# nanobone.net
KiCad netlist of a schematic drawn in EAGLE
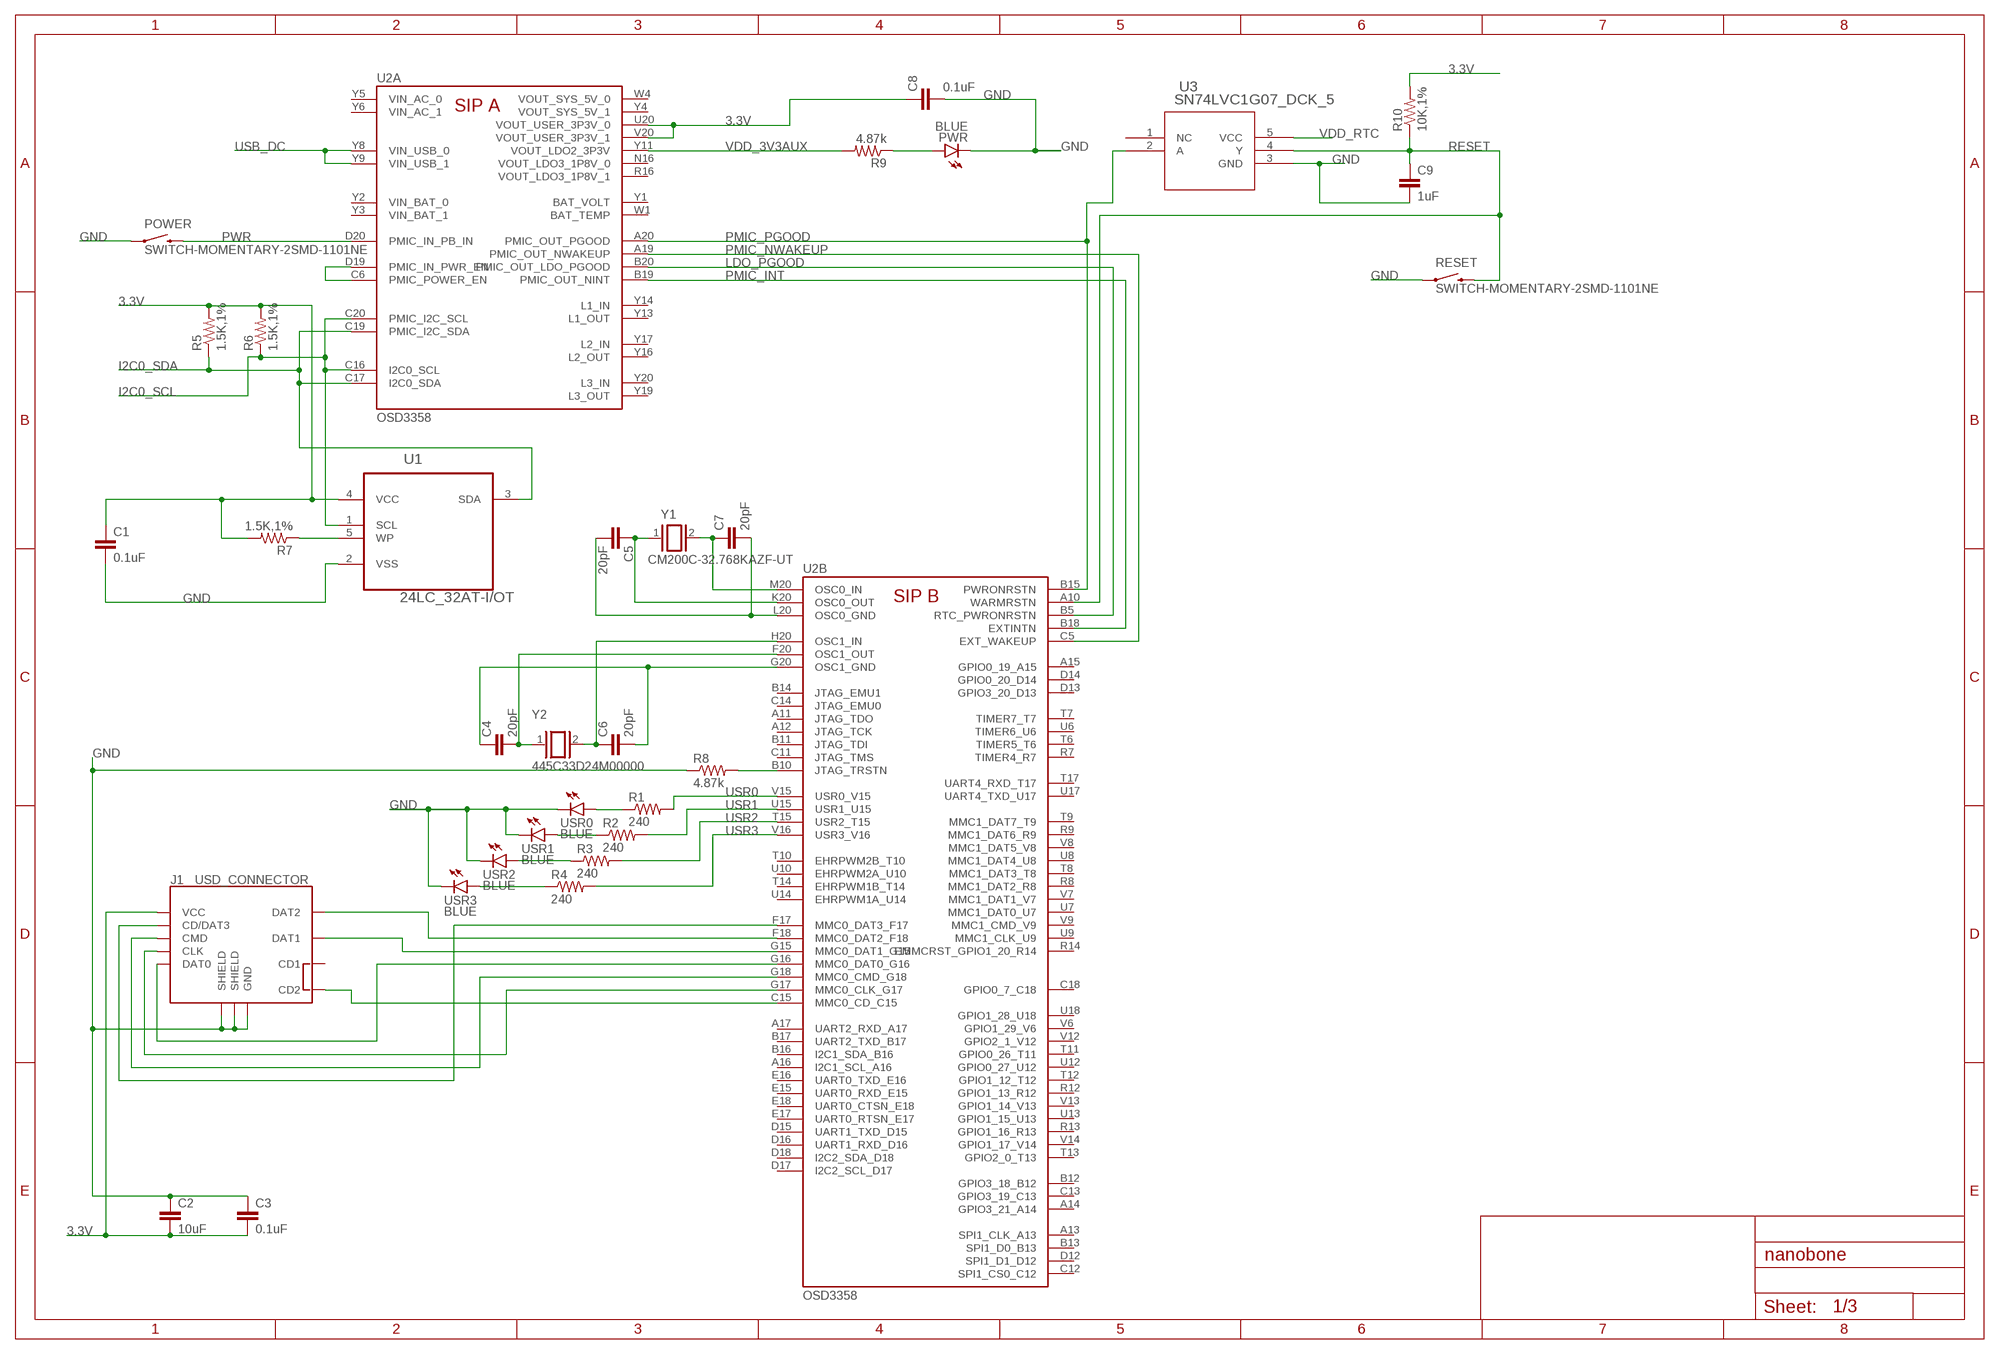
[diagram p0: schematic, sheet 1]
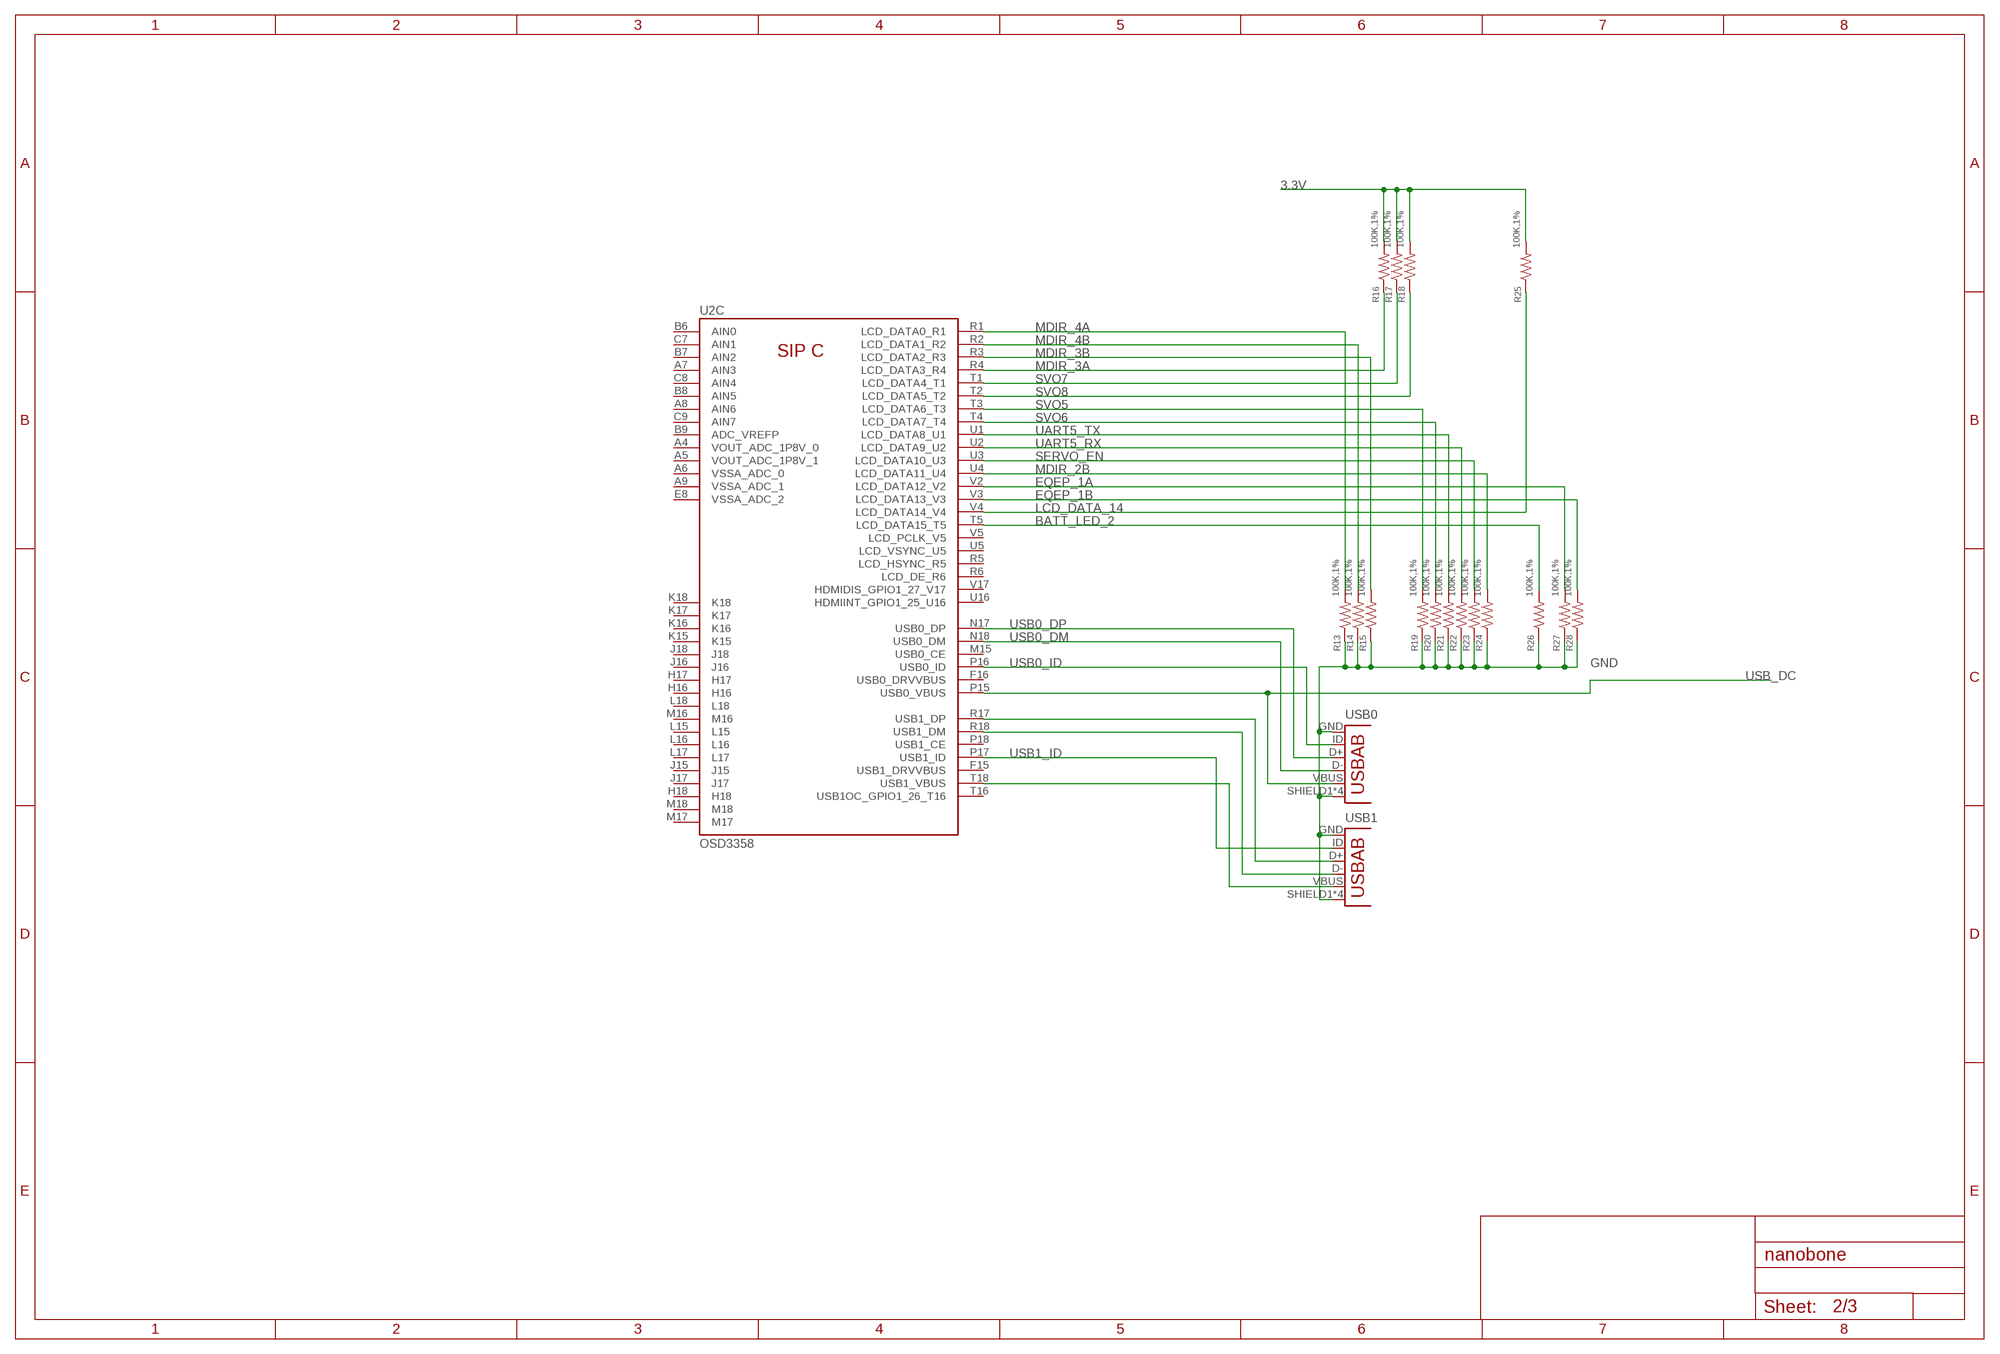
[diagram p1: schematic, sheet 2]
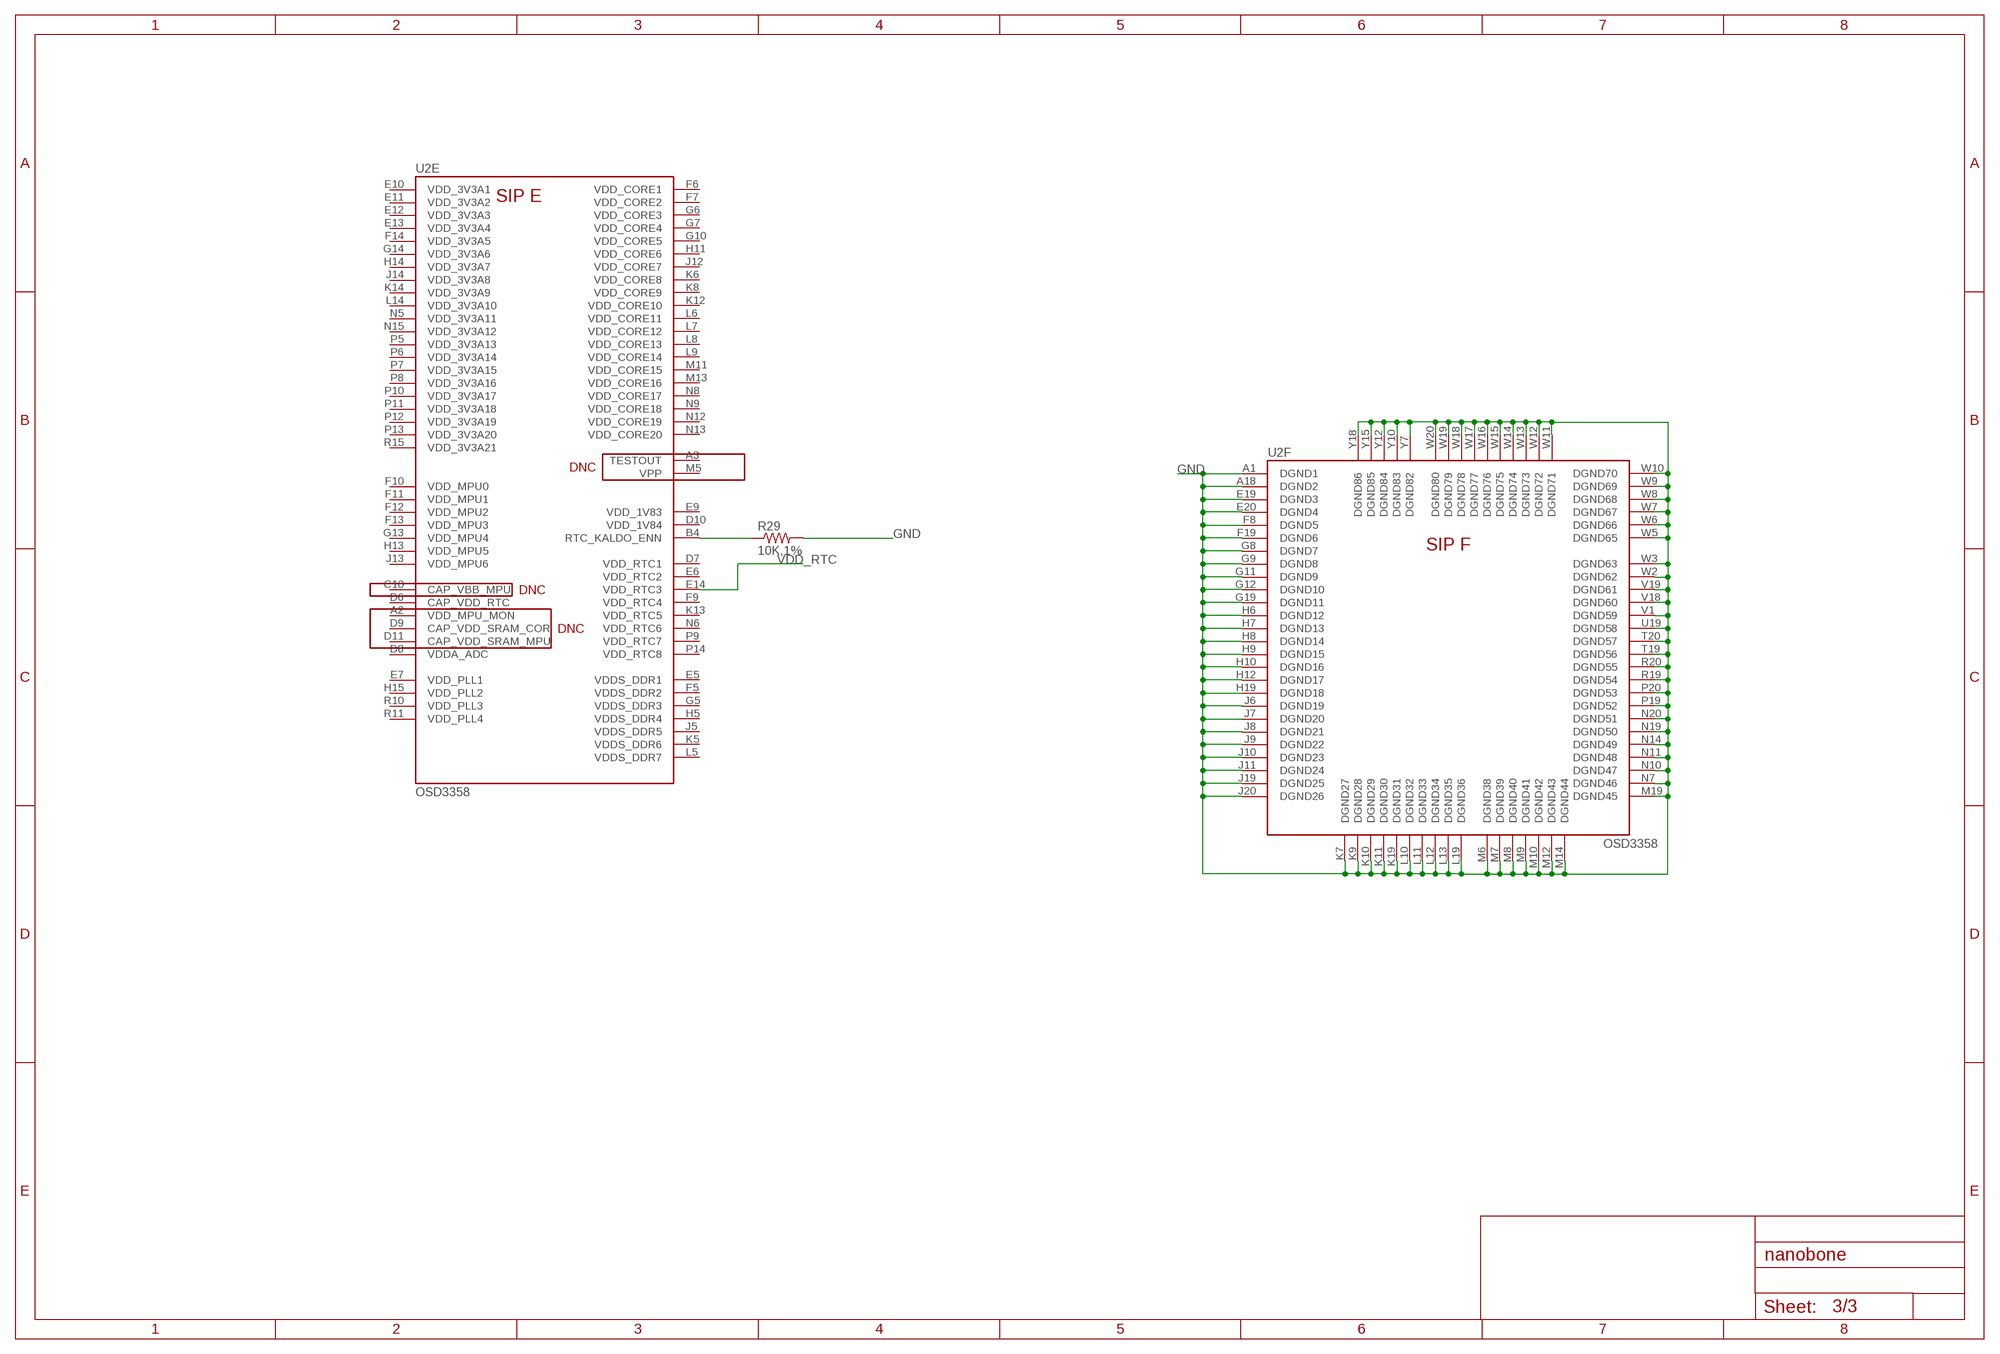
[diagram p2: schematic, sheet 3]

(export (version "E")
  (design (tool "Eeschema 10.0.6"))
  (components
    (comp (ref "R13")
      (value "100K,1%")
      (footprint "eagle-import:0402-RES")
      (libsource (lib "eagle-import") (part "RESISTOR0402-RES"))
    )
    (comp (ref "R14")
      (value "100K,1%")
      (footprint "eagle-import:0402-RES")
      (libsource (lib "eagle-import") (part "RESISTOR0402-RES"))
    )
    (comp (ref "R15")
      (value "100K,1%")
      (footprint "eagle-import:0402-RES")
      (libsource (lib "eagle-import") (part "RESISTOR0402-RES"))
    )
    (comp (ref "R16")
      (value "100K,1%")
      (footprint "eagle-import:0402-RES")
      (libsource (lib "eagle-import") (part "RESISTOR0402-RES"))
    )
    (comp (ref "R17")
      (value "100K,1%")
      (footprint "eagle-import:0402-RES")
      (libsource (lib "eagle-import") (part "RESISTOR0402-RES"))
    )
    (comp (ref "R18")
      (value "100K,1%")
      (footprint "eagle-import:0402-RES")
      (libsource (lib "eagle-import") (part "RESISTOR0402-RES"))
    )
    (comp (ref "R19")
      (value "100K,1%")
      (footprint "eagle-import:0402-RES")
      (libsource (lib "eagle-import") (part "RESISTOR0402-RES"))
    )
    (comp (ref "R20")
      (value "100K,1%")
      (footprint "eagle-import:0402-RES")
      (libsource (lib "eagle-import") (part "RESISTOR0402-RES"))
    )
    (comp (ref "R21")
      (value "100K,1%")
      (footprint "eagle-import:0402-RES")
      (libsource (lib "eagle-import") (part "RESISTOR0402-RES"))
    )
    (comp (ref "R22")
      (value "100K,1%")
      (footprint "eagle-import:0402-RES")
      (libsource (lib "eagle-import") (part "RESISTOR0402-RES"))
    )
    (comp (ref "R23")
      (value "100K,1%")
      (footprint "eagle-import:0402-RES")
      (libsource (lib "eagle-import") (part "RESISTOR0402-RES"))
    )
    (comp (ref "R24")
      (value "100K,1%")
      (footprint "eagle-import:0402-RES")
      (libsource (lib "eagle-import") (part "RESISTOR0402-RES"))
    )
    (comp (ref "R25")
      (value "100K,1%")
      (footprint "eagle-import:0402-RES")
      (libsource (lib "eagle-import") (part "RESISTOR0402-RES"))
    )
    (comp (ref "R26")
      (value "100K,1%")
      (footprint "eagle-import:0402-RES")
      (libsource (lib "eagle-import") (part "RESISTOR0402-RES"))
    )
    (comp (ref "R27")
      (value "100K,1%")
      (footprint "eagle-import:0402-RES")
      (libsource (lib "eagle-import") (part "RESISTOR0402-RES"))
    )
    (comp (ref "R28")
      (value "100K,1%")
      (footprint "eagle-import:0402-RES")
      (libsource (lib "eagle-import") (part "RESISTOR0402-RES"))
    )
    (comp (ref "U2")
      (value "OSD3358")
      (footprint "eagle-import:OSD3358")
      (libsource (lib "eagle-import") (part "OSD3358"))
    )
    (comp (ref "USB0")
      (value "USB-AB")
      (footprint "eagle-import:USB-AB-MICRO-SMD")
      (libsource (lib "eagle-import") (part "USB-AB"))
    )
    (comp (ref "USB1")
      (value "USB-AB")
      (footprint "eagle-import:USB-AB-MICRO-SMD")
      (libsource (lib "eagle-import") (part "USB-AB"))
    )
    (comp (ref "C1")
      (value "0.1uF")
      (footprint "eagle-import:0402-CAP")
      (libsource (lib "eagle-import") (part "CAP0402-CAP"))
    )
    (comp (ref "C2")
      (value "10uF")
      (footprint "eagle-import:0805")
      (libsource (lib "eagle-import") (part "CAP0805"))
    )
    (comp (ref "C3")
      (value "0.1uF")
      (footprint "eagle-import:0402-CAP")
      (libsource (lib "eagle-import") (part "CAP0402-CAP"))
    )
    (comp (ref "C4")
      (value "20pF")
      (footprint "eagle-import:0402-CAP")
      (libsource (lib "eagle-import") (part "CAP0402-CAP"))
    )
    (comp (ref "C5")
      (value "20pF")
      (footprint "eagle-import:0402-CAP")
      (libsource (lib "eagle-import") (part "CAP0402-CAP"))
    )
    (comp (ref "C6")
      (value "20pF")
      (footprint "eagle-import:0402-CAP")
      (libsource (lib "eagle-import") (part "CAP0402-CAP"))
    )
    (comp (ref "C7")
      (value "20pF")
      (footprint "eagle-import:0402-CAP")
      (libsource (lib "eagle-import") (part "CAP0402-CAP"))
    )
    (comp (ref "C8")
      (value "0.1uF")
      (footprint "eagle-import:0402-CAP")
      (libsource (lib "eagle-import") (part "CAP0402-CAP"))
    )
    (comp (ref "C9")
      (value "1uF")
      (footprint "eagle-import:0402-CAP")
      (libsource (lib "eagle-import") (part "CAP0402-CAP"))
    )
    (comp (ref "J1")
      (value "USD_CONNECTOR")
      (footprint "eagle-import:MICRO-SD-SOCKET-PP")
      (libsource (lib "eagle-import") (part "USD_CONNECTOR"))
    )
    (comp (ref "POWER")
      (value "SWITCH-MOMENTARY-2SMD-1101NE")
      (footprint "eagle-import:TACTILE-SWITCH-1101NE")
      (libsource (lib "eagle-import") (part "SWITCH-MOMENTARY-2SMD-1101NE"))
    )
    (comp (ref "PWR")
      (value "BLUE")
      (footprint "eagle-import:0402-LED")
      (libsource (lib "eagle-import") (part "LED0402"))
    )
    (comp (ref "R1")
      (value "240")
      (footprint "eagle-import:0402-RES")
      (libsource (lib "eagle-import") (part "RESISTOR0402-RES"))
    )
    (comp (ref "R2")
      (value "240")
      (footprint "eagle-import:0402-RES")
      (libsource (lib "eagle-import") (part "RESISTOR0402-RES"))
    )
    (comp (ref "R3")
      (value "240")
      (footprint "eagle-import:0402-RES")
      (libsource (lib "eagle-import") (part "RESISTOR0402-RES"))
    )
    (comp (ref "R4")
      (value "240")
      (footprint "eagle-import:0402-RES")
      (libsource (lib "eagle-import") (part "RESISTOR0402-RES"))
    )
    (comp (ref "R5")
      (value "1.5K,1%")
      (footprint "eagle-import:0402-RES")
      (libsource (lib "eagle-import") (part "RESISTOR0402-RES"))
    )
    (comp (ref "R6")
      (value "1.5K,1%")
      (footprint "eagle-import:0402-RES")
      (libsource (lib "eagle-import") (part "RESISTOR0402-RES"))
    )
    (comp (ref "R7")
      (value "1.5K,1%")
      (footprint "eagle-import:0402-RES")
      (libsource (lib "eagle-import") (part "RESISTOR0402-RES"))
    )
    (comp (ref "R8")
      (value "4.87k")
      (footprint "eagle-import:0402-RES")
      (libsource (lib "eagle-import") (part "RESISTOR0402-RES"))
    )
    (comp (ref "R9")
      (value "4.87k")
      (footprint "eagle-import:0402-RES")
      (libsource (lib "eagle-import") (part "RESISTOR0402-RES"))
    )
    (comp (ref "R10")
      (value "10K,1%")
      (footprint "eagle-import:0402-RES")
      (libsource (lib "eagle-import") (part "RESISTOR0402-RES"))
    )
    (comp (ref "RESET")
      (value "SWITCH-MOMENTARY-2SMD-1101NE")
      (footprint "eagle-import:TACTILE-SWITCH-1101NE")
      (libsource (lib "eagle-import") (part "SWITCH-MOMENTARY-2SMD-1101NE"))
    )
    (comp (ref "U1")
      (value "24LC_32AT-I/OT")
      (footprint "eagle-import:SOT95P290X145-5N")
      (fields (field (name "MPN") "24LC32AT-I/OT"))
      (libsource (lib "eagle-import") (part "24LC_32AT-I/OT"))
    )
    (comp (ref "U3")
      (value "SN74LVC1G07_DCK_5")
      (footprint "eagle-import:DCK5")
      (fields
        (field (name "GENERIC_PART_NUMBER") "SN74LVC1G07")
        (field (name "MANUFACTURER") "Texas Instruments")
        (field (name "MANUFACTURER_PART_NUMBER") "sn74lvc1g07_dck_5")
      )
      (libsource (lib "eagle-import") (part "SN74LVC1G07_DCK_5"))
    )
    (comp (ref "USR0")
      (value "BLUE")
      (footprint "eagle-import:0402-LED")
      (libsource (lib "eagle-import") (part "LED0402"))
    )
    (comp (ref "USR1")
      (value "BLUE")
      (footprint "eagle-import:0402-LED")
      (libsource (lib "eagle-import") (part "LED0402"))
    )
    (comp (ref "USR2")
      (value "BLUE")
      (footprint "eagle-import:0402-LED")
      (libsource (lib "eagle-import") (part "LED0402"))
    )
    (comp (ref "USR3")
      (value "BLUE")
      (footprint "eagle-import:0402-LED")
      (libsource (lib "eagle-import") (part "LED0402"))
    )
    (comp (ref "Y1")
      (value "CM200C-32.768KAZF-UT")
      (footprint "eagle-import:CM200C-32.768KAZF-UT")
      (libsource (lib "eagle-import") (part "CM200C-32.768KAZF-UT"))
    )
    (comp (ref "Y2")
      (value "445C33D24M00000")
      (footprint "eagle-import:445C33D24M00000")
      (libsource (lib "eagle-import") (part "445C33D24M00000"))
    )
    (comp (ref "R29")
      (value "10K,1%")
      (footprint "eagle-import:0402-RES")
      (libsource (lib "eagle-import") (part "RESISTOR0402-RES"))
    )
  )
  (nets
    (net (code "1") (name "3.3V") (class "Default")
      (node (ref "C1") (pin "1") (pinfunction "1_1") (pintype "passive"))
      (node (ref "C2") (pin "2") (pinfunction "2_2") (pintype "passive"))
      (node (ref "C3") (pin "2") (pinfunction "2_2") (pintype "passive"))
      (node (ref "C8") (pin "1") (pinfunction "1_1") (pintype "passive"))
      (node (ref "J1") (pin "VCC") (pinfunction "VCC_VCC") (pintype "bidirectional"))
      (node (ref "R10") (pin "2") (pinfunction "2_2") (pintype "passive"))
      (node (ref "R16") (pin "2") (pinfunction "2_2") (pintype "passive"))
      (node (ref "R17") (pin "2") (pinfunction "2_2") (pintype "passive"))
      (node (ref "R18") (pin "2") (pinfunction "2_2") (pintype "passive"))
      (node (ref "R25") (pin "2") (pinfunction "2_2") (pintype "passive"))
      (node (ref "R5") (pin "2") (pinfunction "2_2") (pintype "passive"))
      (node (ref "R6") (pin "2") (pinfunction "2_2") (pintype "passive"))
      (node (ref "R7") (pin "2") (pinfunction "2_2") (pintype "passive"))
      (node (ref "U1") (pin "4") (pinfunction "VCC_4") (pintype "power_in"))
      (node (ref "U2") (pin "U20") (pinfunction "VOUT_USER_3P3V_0_U20") (pintype "power_in"))
      (node (ref "U2") (pin "V20") (pinfunction "VOUT_USER_3P3V_1_V20") (pintype "power_in"))
    )
    (net (code "2") (name "BATT_LED_2") (class "Default")
      (node (ref "R26") (pin "2") (pinfunction "2_2") (pintype "passive"))
      (node (ref "U2") (pin "T5") (pinfunction "LCD_DATA15_T5_T5") (pintype "bidirectional"))
    )
    (net (code "3") (name "EQEP_1A") (class "Default")
      (node (ref "R27") (pin "2") (pinfunction "2_2") (pintype "passive"))
      (node (ref "U2") (pin "V2") (pinfunction "LCD_DATA12_V2_V2") (pintype "bidirectional"))
    )
    (net (code "4") (name "EQEP_1B") (class "Default")
      (node (ref "R28") (pin "2") (pinfunction "2_2") (pintype "passive"))
      (node (ref "U2") (pin "V3") (pinfunction "LCD_DATA13_V3_V3") (pintype "bidirectional"))
    )
    (net (code "5") (name "GND") (class "Default")
      (node (ref "C1") (pin "2") (pinfunction "2_2") (pintype "passive"))
      (node (ref "C2") (pin "1") (pinfunction "1_1") (pintype "passive"))
      (node (ref "C3") (pin "1") (pinfunction "1_1") (pintype "passive"))
      (node (ref "C8") (pin "2") (pinfunction "2_2") (pintype "passive"))
      (node (ref "C9") (pin "2") (pinfunction "2_2") (pintype "passive"))
      (node (ref "J1") (pin "GND") (pinfunction "GND_GND") (pintype "bidirectional"))
      (node (ref "J1") (pin "GND1") (pinfunction "SHIELD_GND1") (pintype "bidirectional"))
      (node (ref "J1") (pin "GND3") (pinfunction "SHIELD_GND3") (pintype "bidirectional"))
      (node (ref "POWER") (pin "1") (pinfunction "1_1") (pintype "passive"))
      (node (ref "PWR") (pin "C") (pinfunction "C_C") (pintype "passive"))
      (node (ref "R13") (pin "1") (pinfunction "1_1") (pintype "passive"))
      (node (ref "R14") (pin "1") (pinfunction "1_1") (pintype "passive"))
      (node (ref "R15") (pin "1") (pinfunction "1_1") (pintype "passive"))
      (node (ref "R19") (pin "1") (pinfunction "1_1") (pintype "passive"))
      (node (ref "R20") (pin "1") (pinfunction "1_1") (pintype "passive"))
      (node (ref "R21") (pin "1") (pinfunction "1_1") (pintype "passive"))
      (node (ref "R22") (pin "1") (pinfunction "1_1") (pintype "passive"))
      (node (ref "R23") (pin "1") (pinfunction "1_1") (pintype "passive"))
      (node (ref "R24") (pin "1") (pinfunction "1_1") (pintype "passive"))
      (node (ref "R26") (pin "1") (pinfunction "1_1") (pintype "passive"))
      (node (ref "R27") (pin "1") (pinfunction "1_1") (pintype "passive"))
      (node (ref "R28") (pin "1") (pinfunction "1_1") (pintype "passive"))
      (node (ref "R29") (pin "2") (pinfunction "2_2") (pintype "passive"))
      (node (ref "R8") (pin "1") (pinfunction "1_1") (pintype "passive"))
      (node (ref "RESET") (pin "1") (pinfunction "1_1") (pintype "passive"))
      (node (ref "U1") (pin "2") (pinfunction "VSS_2") (pintype "passive"))
      (node (ref "U2") (pin "A1") (pinfunction "DGND1_A1") (pintype "bidirectional"))
      (node (ref "U2") (pin "A18") (pinfunction "DGND2_A18") (pintype "bidirectional"))
      (node (ref "U2") (pin "E19") (pinfunction "DGND3_E19") (pintype "bidirectional"))
      (node (ref "U2") (pin "E20") (pinfunction "DGND4_E20") (pintype "bidirectional"))
      (node (ref "U2") (pin "F19") (pinfunction "DGND6_F19") (pintype "bidirectional"))
      (node (ref "U2") (pin "F8") (pinfunction "DGND5_F8") (pintype "bidirectional"))
      (node (ref "U2") (pin "G11") (pinfunction "DGND9_G11") (pintype "bidirectional"))
      (node (ref "U2") (pin "G12") (pinfunction "DGND10_G12") (pintype "bidirectional"))
      (node (ref "U2") (pin "G19") (pinfunction "DGND11_G19") (pintype "bidirectional"))
      (node (ref "U2") (pin "G8") (pinfunction "DGND7_G8") (pintype "bidirectional"))
      (node (ref "U2") (pin "G9") (pinfunction "DGND8_G9") (pintype "bidirectional"))
      (node (ref "U2") (pin "H10") (pinfunction "DGND16_H10") (pintype "bidirectional"))
      (node (ref "U2") (pin "H12") (pinfunction "DGND17_H12") (pintype "bidirectional"))
      (node (ref "U2") (pin "H19") (pinfunction "DGND18_H19") (pintype "bidirectional"))
      (node (ref "U2") (pin "H6") (pinfunction "DGND12_H6") (pintype "bidirectional"))
      (node (ref "U2") (pin "H7") (pinfunction "DGND13_H7") (pintype "bidirectional"))
      (node (ref "U2") (pin "H8") (pinfunction "DGND14_H8") (pintype "bidirectional"))
      (node (ref "U2") (pin "H9") (pinfunction "DGND15_H9") (pintype "bidirectional"))
      (node (ref "U2") (pin "J10") (pinfunction "DGND23_J10") (pintype "bidirectional"))
      (node (ref "U2") (pin "J11") (pinfunction "DGND24_J11") (pintype "bidirectional"))
      (node (ref "U2") (pin "J19") (pinfunction "DGND25_J19") (pintype "bidirectional"))
      (node (ref "U2") (pin "J20") (pinfunction "DGND26_J20") (pintype "bidirectional"))
      (node (ref "U2") (pin "J6") (pinfunction "DGND19_J6") (pintype "bidirectional"))
      (node (ref "U2") (pin "J7") (pinfunction "DGND20_J7") (pintype "bidirectional"))
      (node (ref "U2") (pin "J8") (pinfunction "DGND21_J8") (pintype "bidirectional"))
      (node (ref "U2") (pin "J9") (pinfunction "DGND22_J9") (pintype "bidirectional"))
      (node (ref "U2") (pin "K10") (pinfunction "DGND29_K10") (pintype "bidirectional"))
      (node (ref "U2") (pin "K11") (pinfunction "DGND30_K11") (pintype "bidirectional"))
      (node (ref "U2") (pin "K19") (pinfunction "DGND31_K19") (pintype "bidirectional"))
      (node (ref "U2") (pin "K7") (pinfunction "DGND27_K7") (pintype "bidirectional"))
      (node (ref "U2") (pin "K9") (pinfunction "DGND28_K9") (pintype "bidirectional"))
      (node (ref "U2") (pin "L10") (pinfunction "DGND32_L10") (pintype "bidirectional"))
      (node (ref "U2") (pin "L11") (pinfunction "DGND33_L11") (pintype "bidirectional"))
      (node (ref "U2") (pin "L12") (pinfunction "DGND34_L12") (pintype "bidirectional"))
      (node (ref "U2") (pin "L13") (pinfunction "DGND35_L13") (pintype "bidirectional"))
      (node (ref "U2") (pin "L19") (pinfunction "DGND36_L19") (pintype "bidirectional"))
      (node (ref "U2") (pin "M10") (pinfunction "DGND42_M10") (pintype "bidirectional"))
      (node (ref "U2") (pin "M12") (pinfunction "DGND43_M12") (pintype "bidirectional"))
      (node (ref "U2") (pin "M14") (pinfunction "DGND44_M14") (pintype "bidirectional"))
      (node (ref "U2") (pin "M19") (pinfunction "DGND45_M19") (pintype "bidirectional"))
      (node (ref "U2") (pin "M6") (pinfunction "DGND38_M6") (pintype "bidirectional"))
      (node (ref "U2") (pin "M7") (pinfunction "DGND39_M7") (pintype "bidirectional"))
      (node (ref "U2") (pin "M8") (pinfunction "DGND40_M8") (pintype "bidirectional"))
      (node (ref "U2") (pin "M9") (pinfunction "DGND41_M9") (pintype "bidirectional"))
      (node (ref "U2") (pin "N10") (pinfunction "DGND47_N10") (pintype "bidirectional"))
      (node (ref "U2") (pin "N11") (pinfunction "DGND48_N11") (pintype "bidirectional"))
      (node (ref "U2") (pin "N14") (pinfunction "DGND49_N14") (pintype "bidirectional"))
      (node (ref "U2") (pin "N19") (pinfunction "DGND50_N19") (pintype "bidirectional"))
      (node (ref "U2") (pin "N20") (pinfunction "DGND51_N20") (pintype "bidirectional"))
      (node (ref "U2") (pin "N7") (pinfunction "DGND46_N7") (pintype "bidirectional"))
      (node (ref "U2") (pin "P19") (pinfunction "DGND52_P19") (pintype "bidirectional"))
      (node (ref "U2") (pin "P20") (pinfunction "DGND53_P20") (pintype "bidirectional"))
      (node (ref "U2") (pin "R19") (pinfunction "DGND54_R19") (pintype "bidirectional"))
      (node (ref "U2") (pin "R20") (pinfunction "DGND55_R20") (pintype "bidirectional"))
      (node (ref "U2") (pin "T19") (pinfunction "DGND56_T19") (pintype "bidirectional"))
      (node (ref "U2") (pin "T20") (pinfunction "DGND57_T20") (pintype "bidirectional"))
      (node (ref "U2") (pin "U19") (pinfunction "DGND58_U19") (pintype "bidirectional"))
      (node (ref "U2") (pin "V1") (pinfunction "DGND59_V1") (pintype "bidirectional"))
      (node (ref "U2") (pin "V18") (pinfunction "DGND60_V18") (pintype "bidirectional"))
      (node (ref "U2") (pin "V19") (pinfunction "DGND61_V19") (pintype "bidirectional"))
      (node (ref "U2") (pin "W10") (pinfunction "DGND70_W10") (pintype "bidirectional"))
      (node (ref "U2") (pin "W11") (pinfunction "DGND71_W11") (pintype "bidirectional"))
      (node (ref "U2") (pin "W12") (pinfunction "DGND72_W12") (pintype "bidirectional"))
      (node (ref "U2") (pin "W13") (pinfunction "DGND73_W13") (pintype "bidirectional"))
      (node (ref "U2") (pin "W14") (pinfunction "DGND74_W14") (pintype "bidirectional"))
      (node (ref "U2") (pin "W15") (pinfunction "DGND75_W15") (pintype "bidirectional"))
      (node (ref "U2") (pin "W16") (pinfunction "DGND76_W16") (pintype "bidirectional"))
      (node (ref "U2") (pin "W17") (pinfunction "DGND77_W17") (pintype "bidirectional"))
      (node (ref "U2") (pin "W18") (pinfunction "DGND78_W18") (pintype "bidirectional"))
      (node (ref "U2") (pin "W19") (pinfunction "DGND79_W19") (pintype "bidirectional"))
      (node (ref "U2") (pin "W2") (pinfunction "DGND62_W2") (pintype "bidirectional"))
      (node (ref "U2") (pin "W20") (pinfunction "DGND80_W20") (pintype "bidirectional"))
      (node (ref "U2") (pin "W3") (pinfunction "DGND63_W3") (pintype "bidirectional"))
      (node (ref "U2") (pin "W5") (pinfunction "DGND65_W5") (pintype "bidirectional"))
      (node (ref "U2") (pin "W6") (pinfunction "DGND66_W6") (pintype "bidirectional"))
      (node (ref "U2") (pin "W7") (pinfunction "DGND67_W7") (pintype "bidirectional"))
      (node (ref "U2") (pin "W8") (pinfunction "DGND68_W8") (pintype "bidirectional"))
      (node (ref "U2") (pin "W9") (pinfunction "DGND69_W9") (pintype "bidirectional"))
      (node (ref "U2") (pin "Y10") (pinfunction "DGND83_Y10") (pintype "bidirectional"))
      (node (ref "U2") (pin "Y12") (pinfunction "DGND84_Y12") (pintype "bidirectional"))
      (node (ref "U2") (pin "Y15") (pinfunction "DGND85_Y15") (pintype "bidirectional"))
      (node (ref "U2") (pin "Y18") (pinfunction "DGND86_Y18") (pintype "bidirectional"))
      (node (ref "U2") (pin "Y7") (pinfunction "DGND82_Y7") (pintype "bidirectional"))
      (node (ref "U3") (pin "3") (pinfunction "GND_3") (pintype "power_in"))
      (node (ref "USB0") (pin "GND") (pinfunction "GND_GND") (pintype "bidirectional"))
      (node (ref "USB0") (pin "SHIELD1") (pinfunction "SHIELD_SHIELD1") (pintype "bidirectional"))
      (node (ref "USB0") (pin "SHIELD2") (pinfunction "SHIELD_SHIELD2") (pintype "bidirectional"))
      (node (ref "USB0") (pin "SHIELD3") (pinfunction "SHIELD_SHIELD3") (pintype "bidirectional"))
      (node (ref "USB0") (pin "SHIELD4") (pinfunction "SHIELD_SHIELD4") (pintype "bidirectional"))
      (node (ref "USB1") (pin "GND") (pinfunction "GND_GND") (pintype "bidirectional"))
      (node (ref "USB1") (pin "SHIELD1") (pinfunction "SHIELD_SHIELD1") (pintype "bidirectional"))
      (node (ref "USB1") (pin "SHIELD2") (pinfunction "SHIELD_SHIELD2") (pintype "bidirectional"))
      (node (ref "USB1") (pin "SHIELD3") (pinfunction "SHIELD_SHIELD3") (pintype "bidirectional"))
      (node (ref "USB1") (pin "SHIELD4") (pinfunction "SHIELD_SHIELD4") (pintype "bidirectional"))
      (node (ref "USR0") (pin "C") (pinfunction "C_C") (pintype "passive"))
      (node (ref "USR1") (pin "C") (pinfunction "C_C") (pintype "passive"))
      (node (ref "USR2") (pin "C") (pinfunction "C_C") (pintype "passive"))
      (node (ref "USR3") (pin "C") (pinfunction "C_C") (pintype "passive"))
    )
    (net (code "6") (name "I2C0_SCL") (class "Default")
      (node (ref "R6") (pin "1") (pinfunction "1_1") (pintype "passive"))
      (node (ref "U1") (pin "1") (pinfunction "SCL_1") (pintype "input"))
      (node (ref "U2") (pin "C16") (pinfunction "I2C0_SCL_C16") (pintype "bidirectional"))
      (node (ref "U2") (pin "C20") (pinfunction "PMIC_I2C_SCL_C20") (pintype "bidirectional"))
    )
    (net (code "7") (name "I2C0_SDA") (class "Default")
      (node (ref "R5") (pin "1") (pinfunction "1_1") (pintype "passive"))
      (node (ref "U1") (pin "3") (pinfunction "SDA_3") (pintype "bidirectional"))
      (node (ref "U2") (pin "C17") (pinfunction "I2C0_SDA_C17") (pintype "bidirectional"))
      (node (ref "U2") (pin "C19") (pinfunction "PMIC_I2C_SDA_C19") (pintype "bidirectional"))
    )
    (net (code "8") (name "LCD_DATA_14") (class "Default")
      (node (ref "R25") (pin "1") (pinfunction "1_1") (pintype "passive"))
      (node (ref "U2") (pin "V4") (pinfunction "LCD_DATA14_V4_V4") (pintype "bidirectional"))
    )
    (net (code "9") (name "LDO_PGOOD") (class "Default")
      (node (ref "U2") (pin "B20") (pinfunction "PMIC_OUT_LDO_PGOOD_B20") (pintype "output"))
      (node (ref "U2") (pin "B5") (pinfunction "RTC_PWRONRSTN_B5") (pintype "bidirectional"))
    )
    (net (code "10") (name "MDIR_2B") (class "Default")
      (node (ref "R24") (pin "2") (pinfunction "2_2") (pintype "passive"))
      (node (ref "U2") (pin "U4") (pinfunction "LCD_DATA11_U4_U4") (pintype "bidirectional"))
    )
    (net (code "11") (name "MDIR_3A") (class "Default")
      (node (ref "R16") (pin "1") (pinfunction "1_1") (pintype "passive"))
      (node (ref "U2") (pin "R4") (pinfunction "LCD_DATA3_R4_R4") (pintype "bidirectional"))
    )
    (net (code "12") (name "MDIR_3B") (class "Default")
      (node (ref "R15") (pin "2") (pinfunction "2_2") (pintype "passive"))
      (node (ref "U2") (pin "R3") (pinfunction "LCD_DATA2_R3_R3") (pintype "bidirectional"))
    )
    (net (code "13") (name "MDIR_4A") (class "Default")
      (node (ref "R13") (pin "2") (pinfunction "2_2") (pintype "passive"))
      (node (ref "U2") (pin "R1") (pinfunction "LCD_DATA0_R1_R1") (pintype "bidirectional"))
    )
    (net (code "14") (name "MDIR_4B") (class "Default")
      (node (ref "R14") (pin "2") (pinfunction "2_2") (pintype "passive"))
      (node (ref "U2") (pin "R2") (pinfunction "LCD_DATA1_R2_R2") (pintype "bidirectional"))
    )
    (net (code "15") (name "Net-(PWR-PadA)") (class "Default")
      (node (ref "PWR") (pin "A") (pinfunction "A_A") (pintype "passive"))
      (node (ref "R9") (pin "1") (pinfunction "1_1") (pintype "passive"))
    )
    (net (code "16") (name "Net-(R1-Pad1)") (class "Default")
      (node (ref "R1") (pin "1") (pinfunction "1_1") (pintype "passive"))
      (node (ref "USR0") (pin "A") (pinfunction "A_A") (pintype "passive"))
    )
    (net (code "17") (name "Net-(R2-Pad1)") (class "Default")
      (node (ref "R2") (pin "1") (pinfunction "1_1") (pintype "passive"))
      (node (ref "USR1") (pin "A") (pinfunction "A_A") (pintype "passive"))
    )
    (net (code "18") (name "Net-(R3-Pad1)") (class "Default")
      (node (ref "R3") (pin "1") (pinfunction "1_1") (pintype "passive"))
      (node (ref "USR2") (pin "A") (pinfunction "A_A") (pintype "passive"))
    )
    (net (code "19") (name "Net-(R4-Pad1)") (class "Default")
      (node (ref "R4") (pin "1") (pinfunction "1_1") (pintype "passive"))
      (node (ref "USR3") (pin "A") (pinfunction "A_A") (pintype "passive"))
    )
    (net (code "20") (name "Net-(U1-WP)") (class "Default")
      (node (ref "R7") (pin "1") (pinfunction "1_1") (pintype "passive"))
      (node (ref "U1") (pin "5") (pinfunction "WP_5") (pintype "input"))
    )
    (net (code "21") (name "Net-(U2A-PMIC_IN_PWR_EN)") (class "Default")
      (node (ref "U2") (pin "C6") (pinfunction "PMIC_POWER_EN_C6") (pintype "output"))
      (node (ref "U2") (pin "D19") (pinfunction "PMIC_IN_PWR_EN_D19") (pintype "input"))
    )
    (net (code "22") (name "Net-(U2B-JTAG_TRSTN)") (class "Default")
      (node (ref "R8") (pin "2") (pinfunction "2_2") (pintype "passive"))
      (node (ref "U2") (pin "B10") (pinfunction "JTAG_TRSTN_B10") (pintype "bidirectional"))
    )
    (net (code "23") (name "Net-(U2B-MMC0_CD_C15)") (class "Default")
      (node (ref "J1") (pin "CD2") (pinfunction "CD2_CD2") (pintype "bidirectional"))
      (node (ref "U2") (pin "C15") (pinfunction "MMC0_CD_C15_C15") (pintype "bidirectional"))
    )
    (net (code "24") (name "Net-(U2B-MMC0_CLK_G17)") (class "Default")
      (node (ref "J1") (pin "CLK") (pinfunction "CLK_CLK") (pintype "bidirectional"))
      (node (ref "U2") (pin "G17") (pinfunction "MMC0_CLK_G17_G17") (pintype "bidirectional"))
    )
    (net (code "25") (name "Net-(U2B-MMC0_CMD_G18)") (class "Default")
      (node (ref "J1") (pin "CMD") (pinfunction "CMD_CMD") (pintype "bidirectional"))
      (node (ref "U2") (pin "G18") (pinfunction "MMC0_CMD_G18_G18") (pintype "bidirectional"))
    )
    (net (code "26") (name "Net-(U2B-MMC0_DAT0_G16)") (class "Default")
      (node (ref "J1") (pin "DAT0") (pinfunction "DAT0_DAT0") (pintype "bidirectional"))
      (node (ref "U2") (pin "G16") (pinfunction "MMC0_DAT0_G16_G16") (pintype "bidirectional"))
    )
    (net (code "27") (name "Net-(U2B-MMC0_DAT1_G15)") (class "Default")
      (node (ref "J1") (pin "DAT1") (pinfunction "DAT1_DAT1") (pintype "bidirectional"))
      (node (ref "U2") (pin "G15") (pinfunction "MMC0_DAT1_G15_G15") (pintype "bidirectional"))
    )
    (net (code "28") (name "Net-(U2B-MMC0_DAT2_F18)") (class "Default")
      (node (ref "J1") (pin "DAT2") (pinfunction "DAT2_DAT2") (pintype "bidirectional"))
      (node (ref "U2") (pin "F18") (pinfunction "MMC0_DAT2_F18_F18") (pintype "bidirectional"))
    )
    (net (code "29") (name "Net-(U2B-MMC0_DAT3_F17)") (class "Default")
      (node (ref "J1") (pin "CD/DAT3") (pinfunction "CD/DAT3_CD/DAT3") (pintype "bidirectional"))
      (node (ref "U2") (pin "F17") (pinfunction "MMC0_DAT3_F17_F17") (pintype "bidirectional"))
    )
    (net (code "30") (name "Net-(U2B-OSC0_GND)") (class "Default")
      (node (ref "C5") (pin "2") (pinfunction "2_2") (pintype "passive"))
      (node (ref "C7") (pin "2") (pinfunction "2_2") (pintype "passive"))
      (node (ref "U2") (pin "L20") (pinfunction "OSC0_GND_L20") (pintype "bidirectional"))
    )
    (net (code "31") (name "Net-(U2B-OSC0_IN)") (class "Default")
      (node (ref "C7") (pin "1") (pinfunction "1_1") (pintype "passive"))
      (node (ref "U2") (pin "M20") (pinfunction "OSC0_IN_M20") (pintype "bidirectional"))
      (node (ref "Y1") (pin "2") (pinfunction "2_2") (pintype "passive"))
    )
    (net (code "32") (name "Net-(U2B-OSC0_OUT)") (class "Default")
      (node (ref "C5") (pin "1") (pinfunction "1_1") (pintype "passive"))
      (node (ref "U2") (pin "K20") (pinfunction "OSC0_OUT_K20") (pintype "bidirectional"))
      (node (ref "Y1") (pin "1") (pinfunction "1_1") (pintype "passive"))
    )
    (net (code "33") (name "Net-(U2B-OSC1_GND)") (class "Default")
      (node (ref "C4") (pin "1") (pinfunction "1_1") (pintype "passive"))
      (node (ref "C6") (pin "2") (pinfunction "2_2") (pintype "passive"))
      (node (ref "U2") (pin "G20") (pinfunction "OSC1_GND_G20") (pintype "bidirectional"))
    )
    (net (code "34") (name "Net-(U2B-OSC1_IN)") (class "Default")
      (node (ref "C6") (pin "1") (pinfunction "1_1") (pintype "passive"))
      (node (ref "U2") (pin "H20") (pinfunction "OSC1_IN_H20") (pintype "bidirectional"))
      (node (ref "Y2") (pin "2") (pinfunction "2_2") (pintype "passive"))
    )
    (net (code "35") (name "Net-(U2B-OSC1_OUT)") (class "Default")
      (node (ref "C4") (pin "2") (pinfunction "2_2") (pintype "passive"))
      (node (ref "U2") (pin "F20") (pinfunction "OSC1_OUT_F20") (pintype "bidirectional"))
      (node (ref "Y2") (pin "1") (pinfunction "1_1") (pintype "passive"))
    )
    (net (code "36") (name "Net-(U2C-USB1_DM)") (class "Default")
      (node (ref "U2") (pin "R18") (pinfunction "USB1_DM_R18") (pintype "bidirectional"))
      (node (ref "USB1") (pin "D-") (pinfunction "D-_D-") (pintype "bidirectional"))
    )
    (net (code "37") (name "Net-(U2C-USB1_DP)") (class "Default")
      (node (ref "U2") (pin "R17") (pinfunction "USB1_DP_R17") (pintype "bidirectional"))
      (node (ref "USB1") (pin "D+") (pinfunction "D+_D+") (pintype "bidirectional"))
    )
    (net (code "38") (name "Net-(U2C-USB1_VBUS)") (class "Default")
      (node (ref "U2") (pin "T18") (pinfunction "USB1_VBUS_T18") (pintype "bidirectional"))
      (node (ref "USB1") (pin "VBUS") (pinfunction "VBUS_VBUS") (pintype "bidirectional"))
    )
    (net (code "39") (name "Net-(U2E-RTC_KALDO_ENN)") (class "Default")
      (node (ref "R29") (pin "1") (pinfunction "1_1") (pintype "passive"))
      (node (ref "U2") (pin "B4") (pinfunction "RTC_KALDO_ENN_B4") (pintype "bidirectional"))
    )
    (net (code "40") (name "PMIC_INT") (class "Default")
      (node (ref "U2") (pin "B18") (pinfunction "EXTINTN_B18") (pintype "bidirectional"))
      (node (ref "U2") (pin "B19") (pinfunction "PMIC_OUT_NINT_B19") (pintype "output"))
    )
    (net (code "41") (name "PMIC_NWAKEUP") (class "Default")
      (node (ref "U2") (pin "A19") (pinfunction "PMIC_OUT_NWAKEUP_A19") (pintype "output"))
      (node (ref "U2") (pin "C5") (pinfunction "EXT_WAKEUP_C5") (pintype "bidirectional"))
    )
    (net (code "42") (name "PMIC_PGOOD") (class "Default")
      (node (ref "U2") (pin "A20") (pinfunction "PMIC_OUT_PGOOD_A20") (pintype "output"))
      (node (ref "U2") (pin "B15") (pinfunction "PWRONRSTN_B15") (pintype "bidirectional"))
      (node (ref "U3") (pin "2") (pinfunction "A_2") (pintype "input"))
    )
    (net (code "43") (name "PWR") (class "Default")
      (node (ref "POWER") (pin "2") (pinfunction "2_2") (pintype "passive"))
      (node (ref "U2") (pin "D20") (pinfunction "PMIC_IN_PB_IN_D20") (pintype "bidirectional"))
    )
    (net (code "44") (name "RESET") (class "Default")
      (node (ref "C9") (pin "1") (pinfunction "1_1") (pintype "passive"))
      (node (ref "R10") (pin "1") (pinfunction "1_1") (pintype "passive"))
      (node (ref "RESET") (pin "2") (pinfunction "2_2") (pintype "passive"))
      (node (ref "U2") (pin "A10") (pinfunction "WARMRSTN_A10") (pintype "bidirectional"))
      (node (ref "U3") (pin "4") (pinfunction "Y_4") (pintype "output"))
    )
    (net (code "45") (name "SERVO_EN") (class "Default")
      (node (ref "R23") (pin "2") (pinfunction "2_2") (pintype "passive"))
      (node (ref "U2") (pin "U3") (pinfunction "LCD_DATA10_U3_U3") (pintype "bidirectional"))
    )
    (net (code "46") (name "SVO5") (class "Default")
      (node (ref "R19") (pin "2") (pinfunction "2_2") (pintype "passive"))
      (node (ref "U2") (pin "T3") (pinfunction "LCD_DATA6_T3_T3") (pintype "bidirectional"))
    )
    (net (code "47") (name "SVO6") (class "Default")
      (node (ref "R20") (pin "2") (pinfunction "2_2") (pintype "passive"))
      (node (ref "U2") (pin "T4") (pinfunction "LCD_DATA7_T4_T4") (pintype "bidirectional"))
    )
    (net (code "48") (name "SVO7") (class "Default")
      (node (ref "R17") (pin "1") (pinfunction "1_1") (pintype "passive"))
      (node (ref "U2") (pin "T1") (pinfunction "LCD_DATA4_T1_T1") (pintype "bidirectional"))
    )
    (net (code "49") (name "SVO8") (class "Default")
      (node (ref "R18") (pin "1") (pinfunction "1_1") (pintype "passive"))
      (node (ref "U2") (pin "T2") (pinfunction "LCD_DATA5_T2_T2") (pintype "bidirectional"))
    )
    (net (code "50") (name "UART5_RX") (class "Default")
      (node (ref "R22") (pin "2") (pinfunction "2_2") (pintype "passive"))
      (node (ref "U2") (pin "U2") (pinfunction "LCD_DATA9_U2_U2") (pintype "bidirectional"))
    )
    (net (code "51") (name "UART5_TX") (class "Default")
      (node (ref "R21") (pin "2") (pinfunction "2_2") (pintype "passive"))
      (node (ref "U2") (pin "U1") (pinfunction "LCD_DATA8_U1_U1") (pintype "bidirectional"))
    )
    (net (code "52") (name "USB0_DM") (class "Default")
      (node (ref "U2") (pin "N18") (pinfunction "USB0_DM_N18") (pintype "bidirectional"))
      (node (ref "USB0") (pin "D-") (pinfunction "D-_D-") (pintype "bidirectional"))
    )
    (net (code "53") (name "USB0_DP") (class "Default")
      (node (ref "U2") (pin "N17") (pinfunction "USB0_DP_N17") (pintype "bidirectional"))
      (node (ref "USB0") (pin "D+") (pinfunction "D+_D+") (pintype "bidirectional"))
    )
    (net (code "54") (name "USB0_ID") (class "Default")
      (node (ref "U2") (pin "P16") (pinfunction "USB0_ID_P16") (pintype "bidirectional"))
      (node (ref "USB0") (pin "ID") (pinfunction "USBID_ID") (pintype "bidirectional"))
    )
    (net (code "55") (name "USB1_ID") (class "Default")
      (node (ref "U2") (pin "P17") (pinfunction "USB1_ID_P17") (pintype "bidirectional"))
      (node (ref "USB1") (pin "ID") (pinfunction "USBID_ID") (pintype "bidirectional"))
    )
    (net (code "56") (name "USB_DC") (class "Default")
      (node (ref "U2") (pin "P15") (pinfunction "USB0_VBUS_P15") (pintype "bidirectional"))
      (node (ref "U2") (pin "Y8") (pinfunction "VIN_USB_0_Y8") (pintype "power_in"))
      (node (ref "U2") (pin "Y9") (pinfunction "VIN_USB_1_Y9") (pintype "power_in"))
      (node (ref "USB0") (pin "VBUS") (pinfunction "VBUS_VBUS") (pintype "bidirectional"))
    )
    (net (code "57") (name "USR0") (class "Default")
      (node (ref "R1") (pin "2") (pinfunction "2_2") (pintype "passive"))
      (node (ref "U2") (pin "V15") (pinfunction "USR0_V15_V15") (pintype "bidirectional"))
    )
    (net (code "58") (name "USR1") (class "Default")
      (node (ref "R2") (pin "2") (pinfunction "2_2") (pintype "passive"))
      (node (ref "U2") (pin "U15") (pinfunction "USR1_U15_U15") (pintype "bidirectional"))
    )
    (net (code "59") (name "USR2") (class "Default")
      (node (ref "R3") (pin "2") (pinfunction "2_2") (pintype "passive"))
      (node (ref "U2") (pin "T15") (pinfunction "USR2_T15_T15") (pintype "bidirectional"))
    )
    (net (code "60") (name "USR3") (class "Default")
      (node (ref "R4") (pin "2") (pinfunction "2_2") (pintype "passive"))
      (node (ref "U2") (pin "V16") (pinfunction "USR3_V16_V16") (pintype "bidirectional"))
    )
    (net (code "61") (name "VDD_3V3AUX") (class "Default")
      (node (ref "R9") (pin "2") (pinfunction "2_2") (pintype "passive"))
      (node (ref "U2") (pin "Y11") (pinfunction "VOUT_LDO2_3P3V_Y11") (pintype "power_in"))
    )
    (net (code "62") (name "VDD_RTC") (class "Default")
      (node (ref "U2") (pin "E14") (pinfunction "VDD_RTC3_E14") (pintype "bidirectional"))
      (node (ref "U3") (pin "5") (pinfunction "VCC_5") (pintype "power_in"))
    )
    (net (code "63") (name "VIN_AC_0") (class "Default")
      (node (ref "U2") (pin "Y5") (pinfunction "VIN_AC_0_Y5") (pintype "power_in"))
    )
    (net (code "64") (name "VIN_AC_1") (class "Default")
      (node (ref "U2") (pin "Y6") (pinfunction "VIN_AC_1_Y6") (pintype "power_in"))
    )
    (net (code "65") (name "VIN_BAT_0") (class "Default")
      (node (ref "U2") (pin "Y2") (pinfunction "VIN_BAT_0_Y2") (pintype "power_in"))
    )
    (net (code "66") (name "VIN_BAT_1") (class "Default")
      (node (ref "U2") (pin "Y3") (pinfunction "VIN_BAT_1_Y3") (pintype "power_in"))
    )
    (net (code "67") (name "VOUT_LDO3_1P8V_0") (class "Default")
      (node (ref "U2") (pin "N16") (pinfunction "VOUT_LDO3_1P8V_0_N16") (pintype "power_in"))
    )
    (net (code "68") (name "VOUT_LDO3_1P8V_1") (class "Default")
      (node (ref "U2") (pin "R16") (pinfunction "VOUT_LDO3_1P8V_1_R16") (pintype "power_in"))
    )
    (net (code "69") (name "VOUT_SYS_5V_0") (class "Default")
      (node (ref "U2") (pin "W4") (pinfunction "VOUT_SYS_5V_0_W4") (pintype "power_in"))
    )
    (net (code "70") (name "VOUT_SYS_5V_1") (class "Default")
      (node (ref "U2") (pin "Y4") (pinfunction "VOUT_SYS_5V_1_Y4") (pintype "power_in"))
    )
    (net (code "71") (name "unconnected-(J1-PadCD1)") (class "Default")
      (node (ref "J1") (pin "CD1") (pinfunction "CD1_CD1") (pintype "bidirectional"))
    )
    (net (code "72") (name "unconnected-(U2-PadH16)") (class "Default")
      (node (ref "U2") (pin "H16") (pinfunction "H16_H16") (pintype "bidirectional"))
    )
    (net (code "73") (name "unconnected-(U2-PadH17)") (class "Default")
      (node (ref "U2") (pin "H17") (pinfunction "H17_H17") (pintype "bidirectional"))
    )
    (net (code "74") (name "unconnected-(U2-PadH18)") (class "Default")
      (node (ref "U2") (pin "H18") (pinfunction "H18_H18") (pintype "bidirectional"))
    )
    (net (code "75") (name "unconnected-(U2-PadJ15)") (class "Default")
      (node (ref "U2") (pin "J15") (pinfunction "J15_J15") (pintype "bidirectional"))
    )
    (net (code "76") (name "unconnected-(U2-PadJ16)") (class "Default")
      (node (ref "U2") (pin "J16") (pinfunction "J16_J16") (pintype "bidirectional"))
    )
    (net (code "77") (name "unconnected-(U2-PadJ17)") (class "Default")
      (node (ref "U2") (pin "J17") (pinfunction "J17_J17") (pintype "bidirectional"))
    )
    (net (code "78") (name "unconnected-(U2-PadJ18)") (class "Default")
      (node (ref "U2") (pin "J18") (pinfunction "J18_J18") (pintype "bidirectional"))
    )
    (net (code "79") (name "unconnected-(U2-PadK15)") (class "Default")
      (node (ref "U2") (pin "K15") (pinfunction "K15_K15") (pintype "bidirectional"))
    )
    (net (code "80") (name "unconnected-(U2-PadK16)") (class "Default")
      (node (ref "U2") (pin "K16") (pinfunction "K16_K16") (pintype "bidirectional"))
    )
    (net (code "81") (name "unconnected-(U2-PadK17)") (class "Default")
      (node (ref "U2") (pin "K17") (pinfunction "K17_K17") (pintype "bidirectional"))
    )
    (net (code "82") (name "unconnected-(U2-PadK18)") (class "Default")
      (node (ref "U2") (pin "K18") (pinfunction "K18_K18") (pintype "bidirectional"))
    )
    (net (code "83") (name "unconnected-(U2-PadL15)") (class "Default")
      (node (ref "U2") (pin "L15") (pinfunction "L15_L15") (pintype "bidirectional"))
    )
    (net (code "84") (name "unconnected-(U2-PadL16)") (class "Default")
      (node (ref "U2") (pin "L16") (pinfunction "L16_L16") (pintype "bidirectional"))
    )
    (net (code "85") (name "unconnected-(U2-PadL17)") (class "Default")
      (node (ref "U2") (pin "L17") (pinfunction "L17_L17") (pintype "bidirectional"))
    )
    (net (code "86") (name "unconnected-(U2-PadL18)") (class "Default")
      (node (ref "U2") (pin "L18") (pinfunction "L18_L18") (pintype "bidirectional"))
    )
    (net (code "87") (name "unconnected-(U2-PadM16)") (class "Default")
      (node (ref "U2") (pin "M16") (pinfunction "M16_M16") (pintype "bidirectional"))
    )
    (net (code "88") (name "unconnected-(U2-PadM17)") (class "Default")
      (node (ref "U2") (pin "M17") (pinfunction "M17_M17") (pintype "bidirectional"))
    )
    (net (code "89") (name "unconnected-(U2-PadM18)") (class "Default")
      (node (ref "U2") (pin "M18") (pinfunction "M18_M18") (pintype "bidirectional"))
    )
    (net (code "90") (name "unconnected-(U2A-BAT_TEMP-PadW1)") (class "Default")
      (node (ref "U2") (pin "W1") (pinfunction "BAT_TEMP_W1") (pintype "bidirectional"))
    )
    (net (code "91") (name "unconnected-(U2A-BAT_VOLT-PadY1)") (class "Default")
      (node (ref "U2") (pin "Y1") (pinfunction "BAT_VOLT_Y1") (pintype "bidirectional"))
    )
    (net (code "92") (name "unconnected-(U2A-L1_IN-PadY14)") (class "Default")
      (node (ref "U2") (pin "Y14") (pinfunction "L1_IN_Y14") (pintype "bidirectional"))
    )
    (net (code "93") (name "unconnected-(U2A-L1_OUT-PadY13)") (class "Default")
      (node (ref "U2") (pin "Y13") (pinfunction "L1_OUT_Y13") (pintype "bidirectional"))
    )
    (net (code "94") (name "unconnected-(U2A-L2_IN-PadY17)") (class "Default")
      (node (ref "U2") (pin "Y17") (pinfunction "L2_IN_Y17") (pintype "bidirectional"))
    )
    (net (code "95") (name "unconnected-(U2A-L2_OUT-PadY16)") (class "Default")
      (node (ref "U2") (pin "Y16") (pinfunction "L2_OUT_Y16") (pintype "bidirectional"))
    )
    (net (code "96") (name "unconnected-(U2A-L3_IN-PadY20)") (class "Default")
      (node (ref "U2") (pin "Y20") (pinfunction "L3_IN_Y20") (pintype "bidirectional"))
    )
    (net (code "97") (name "unconnected-(U2A-L3_OUT-PadY19)") (class "Default")
      (node (ref "U2") (pin "Y19") (pinfunction "L3_OUT_Y19") (pintype "bidirectional"))
    )
    (net (code "98") (name "unconnected-(U2B-EHRPWM1A_U14-PadU14)") (class "Default")
      (node (ref "U2") (pin "U14") (pinfunction "EHRPWM1A_U14_U14") (pintype "bidirectional"))
    )
    (net (code "99") (name "unconnected-(U2B-EHRPWM1B_T14-PadT14)") (class "Default")
      (node (ref "U2") (pin "T14") (pinfunction "EHRPWM1B_T14_T14") (pintype "bidirectional"))
    )
    (net (code "100") (name "unconnected-(U2B-EHRPWM2A_U10-PadU10)") (class "Default")
      (node (ref "U2") (pin "U10") (pinfunction "EHRPWM2A_U10_U10") (pintype "bidirectional"))
    )
    (net (code "101") (name "unconnected-(U2B-EHRPWM2B_T10-PadT10)") (class "Default")
      (node (ref "U2") (pin "T10") (pinfunction "EHRPWM2B_T10_T10") (pintype "bidirectional"))
    )
    (net (code "102") (name "unconnected-(U2B-EMMCRST_GPIO1_20_R14-PadR14)") (class "Default")
      (node (ref "U2") (pin "R14") (pinfunction "EMMCRST_GPIO1_20_R14_R14") (pintype "bidirectional"))
    )
    (net (code "103") (name "unconnected-(U2B-GPIO0_7_C18-PadC18)") (class "Default")
      (node (ref "U2") (pin "C18") (pinfunction "GPIO0_7_C18_C18") (pintype "bidirectional"))
    )
    (net (code "104") (name "unconnected-(U2B-GPIO0_19_A15-PadA15)") (class "Default")
      (node (ref "U2") (pin "A15") (pinfunction "GPIO0_19_A15_A15") (pintype "bidirectional"))
    )
    (net (code "105") (name "unconnected-(U2B-GPIO0_20_D14-PadD14)") (class "Default")
      (node (ref "U2") (pin "D14") (pinfunction "GPIO0_20_D14_D14") (pintype "bidirectional"))
    )
    (net (code "106") (name "unconnected-(U2B-GPIO0_26_T11-PadT11)") (class "Default")
      (node (ref "U2") (pin "T11") (pinfunction "GPIO0_26_T11_T11") (pintype "bidirectional"))
    )
    (net (code "107") (name "unconnected-(U2B-GPIO0_27_U12-PadU12)") (class "Default")
      (node (ref "U2") (pin "U12") (pinfunction "GPIO0_27_U12_U12") (pintype "bidirectional"))
    )
    (net (code "108") (name "unconnected-(U2B-GPIO1_12_T12-PadT12)") (class "Default")
      (node (ref "U2") (pin "T12") (pinfunction "GPIO1_12_T12_T12") (pintype "bidirectional"))
    )
    (net (code "109") (name "unconnected-(U2B-GPIO1_13_R12-PadR12)") (class "Default")
      (node (ref "U2") (pin "R12") (pinfunction "GPIO1_13_R12_R12") (pintype "bidirectional"))
    )
    (net (code "110") (name "unconnected-(U2B-GPIO1_14_V13-PadV13)") (class "Default")
      (node (ref "U2") (pin "V13") (pinfunction "GPIO1_14_V13_V13") (pintype "bidirectional"))
    )
    (net (code "111") (name "unconnected-(U2B-GPIO1_15_U13-PadU13)") (class "Default")
      (node (ref "U2") (pin "U13") (pinfunction "GPIO1_15_U13_U13") (pintype "bidirectional"))
    )
    (net (code "112") (name "unconnected-(U2B-GPIO1_16_R13-PadR13)") (class "Default")
      (node (ref "U2") (pin "R13") (pinfunction "GPIO1_16_R13_R13") (pintype "bidirectional"))
    )
    (net (code "113") (name "unconnected-(U2B-GPIO1_17_V14-PadV14)") (class "Default")
      (node (ref "U2") (pin "V14") (pinfunction "GPIO1_17_V14_V14") (pintype "bidirectional"))
    )
    (net (code "114") (name "unconnected-(U2B-GPIO1_28_U18-PadU18)") (class "Default")
      (node (ref "U2") (pin "U18") (pinfunction "GPIO1_28_U18_U18") (pintype "bidirectional"))
    )
    (net (code "115") (name "unconnected-(U2B-GPIO1_29_V6-PadV6)") (class "Default")
      (node (ref "U2") (pin "V6") (pinfunction "GPIO1_29_V6_V6") (pintype "bidirectional"))
    )
    (net (code "116") (name "unconnected-(U2B-GPIO2_0_T13-PadT13)") (class "Default")
      (node (ref "U2") (pin "T13") (pinfunction "GPIO2_0_T13_T13") (pintype "bidirectional"))
    )
    (net (code "117") (name "unconnected-(U2B-GPIO2_1_V12-PadV12)") (class "Default")
      (node (ref "U2") (pin "V12") (pinfunction "GPIO2_1_V12_V12") (pintype "bidirectional"))
    )
    (net (code "118") (name "unconnected-(U2B-GPIO3_18_B12-PadB12)") (class "Default")
      (node (ref "U2") (pin "B12") (pinfunction "GPIO3_18_B12_B12") (pintype "bidirectional"))
    )
    (net (code "119") (name "unconnected-(U2B-GPIO3_19_C13-PadC13)") (class "Default")
      (node (ref "U2") (pin "C13") (pinfunction "GPIO3_19_C13_C13") (pintype "bidirectional"))
    )
    (net (code "120") (name "unconnected-(U2B-GPIO3_20_D13-PadD13)") (class "Default")
      (node (ref "U2") (pin "D13") (pinfunction "GPIO3_20_D13_D13") (pintype "bidirectional"))
    )
    (net (code "121") (name "unconnected-(U2B-GPIO3_21_A14-PadA14)") (class "Default")
      (node (ref "U2") (pin "A14") (pinfunction "GPIO3_21_A14_A14") (pintype "bidirectional"))
    )
    (net (code "122") (name "unconnected-(U2B-I2C1_SCL_A16-PadA16)") (class "Default")
      (node (ref "U2") (pin "A16") (pinfunction "I2C1_SCL_A16_A16") (pintype "bidirectional"))
    )
    (net (code "123") (name "unconnected-(U2B-I2C1_SDA_B16-PadB16)") (class "Default")
      (node (ref "U2") (pin "B16") (pinfunction "I2C1_SDA_B16_B16") (pintype "bidirectional"))
    )
    (net (code "124") (name "unconnected-(U2B-I2C2_SCL_D17-PadD17)") (class "Default")
      (node (ref "U2") (pin "D17") (pinfunction "I2C2_SCL_D17_D17") (pintype "bidirectional"))
    )
    (net (code "125") (name "unconnected-(U2B-I2C2_SDA_D18-PadD18)") (class "Default")
      (node (ref "U2") (pin "D18") (pinfunction "I2C2_SDA_D18_D18") (pintype "bidirectional"))
    )
    (net (code "126") (name "unconnected-(U2B-JTAG_EMU0-PadC14)") (class "Default")
      (node (ref "U2") (pin "C14") (pinfunction "JTAG_EMU0_C14") (pintype "bidirectional"))
    )
    (net (code "127") (name "unconnected-(U2B-JTAG_EMU1-PadB14)") (class "Default")
      (node (ref "U2") (pin "B14") (pinfunction "JTAG_EMU1_B14") (pintype "bidirectional"))
    )
    (net (code "128") (name "unconnected-(U2B-JTAG_TCK-PadA12)") (class "Default")
      (node (ref "U2") (pin "A12") (pinfunction "JTAG_TCK_A12") (pintype "bidirectional"))
    )
    (net (code "129") (name "unconnected-(U2B-JTAG_TDI-PadB11)") (class "Default")
      (node (ref "U2") (pin "B11") (pinfunction "JTAG_TDI_B11") (pintype "bidirectional"))
    )
    (net (code "130") (name "unconnected-(U2B-JTAG_TDO-PadA11)") (class "Default")
      (node (ref "U2") (pin "A11") (pinfunction "JTAG_TDO_A11") (pintype "bidirectional"))
    )
    (net (code "131") (name "unconnected-(U2B-JTAG_TMS-PadC11)") (class "Default")
      (node (ref "U2") (pin "C11") (pinfunction "JTAG_TMS_C11") (pintype "bidirectional"))
    )
    (net (code "132") (name "unconnected-(U2B-MMC1_CLK_U9-PadU9)") (class "Default")
      (node (ref "U2") (pin "U9") (pinfunction "MMC1_CLK_U9_U9") (pintype "bidirectional"))
    )
    (net (code "133") (name "unconnected-(U2B-MMC1_CMD_V9-PadV9)") (class "Default")
      (node (ref "U2") (pin "V9") (pinfunction "MMC1_CMD_V9_V9") (pintype "bidirectional"))
    )
    (net (code "134") (name "unconnected-(U2B-MMC1_DAT0_U7-PadU7)") (class "Default")
      (node (ref "U2") (pin "U7") (pinfunction "MMC1_DAT0_U7_U7") (pintype "bidirectional"))
    )
    (net (code "135") (name "unconnected-(U2B-MMC1_DAT1_V7-PadV7)") (class "Default")
      (node (ref "U2") (pin "V7") (pinfunction "MMC1_DAT1_V7_V7") (pintype "bidirectional"))
    )
    (net (code "136") (name "unconnected-(U2B-MMC1_DAT2_R8-PadR8)") (class "Default")
      (node (ref "U2") (pin "R8") (pinfunction "MMC1_DAT2_R8_R8") (pintype "bidirectional"))
    )
    (net (code "137") (name "unconnected-(U2B-MMC1_DAT3_T8-PadT8)") (class "Default")
      (node (ref "U2") (pin "T8") (pinfunction "MMC1_DAT3_T8_T8") (pintype "bidirectional"))
    )
    (net (code "138") (name "unconnected-(U2B-MMC1_DAT4_U8-PadU8)") (class "Default")
      (node (ref "U2") (pin "U8") (pinfunction "MMC1_DAT4_U8_U8") (pintype "bidirectional"))
    )
    (net (code "139") (name "unconnected-(U2B-MMC1_DAT5_V8-PadV8)") (class "Default")
      (node (ref "U2") (pin "V8") (pinfunction "MMC1_DAT5_V8_V8") (pintype "bidirectional"))
    )
    (net (code "140") (name "unconnected-(U2B-MMC1_DAT6_R9-PadR9)") (class "Default")
      (node (ref "U2") (pin "R9") (pinfunction "MMC1_DAT6_R9_R9") (pintype "bidirectional"))
    )
    (net (code "141") (name "unconnected-(U2B-MMC1_DAT7_T9-PadT9)") (class "Default")
      (node (ref "U2") (pin "T9") (pinfunction "MMC1_DAT7_T9_T9") (pintype "bidirectional"))
    )
    (net (code "142") (name "unconnected-(U2B-SPI1_CLK_A13-PadA13)") (class "Default")
      (node (ref "U2") (pin "A13") (pinfunction "SPI1_CLK_A13_A13") (pintype "bidirectional"))
    )
    (net (code "143") (name "unconnected-(U2B-SPI1_CS0_C12-PadC12)") (class "Default")
      (node (ref "U2") (pin "C12") (pinfunction "SPI1_CS0_C12_C12") (pintype "bidirectional"))
    )
    (net (code "144") (name "unconnected-(U2B-SPI1_D0_B13-PadB13)") (class "Default")
      (node (ref "U2") (pin "B13") (pinfunction "SPI1_D0_B13_B13") (pintype "bidirectional"))
    )
    (net (code "145") (name "unconnected-(U2B-SPI1_D1_D12-PadD12)") (class "Default")
      (node (ref "U2") (pin "D12") (pinfunction "SPI1_D1_D12_D12") (pintype "bidirectional"))
    )
    (net (code "146") (name "unconnected-(U2B-TIMER4_R7-PadR7)") (class "Default")
      (node (ref "U2") (pin "R7") (pinfunction "TIMER4_R7_R7") (pintype "bidirectional"))
    )
    (net (code "147") (name "unconnected-(U2B-TIMER5_T6-PadT6)") (class "Default")
      (node (ref "U2") (pin "T6") (pinfunction "TIMER5_T6_T6") (pintype "bidirectional"))
    )
    (net (code "148") (name "unconnected-(U2B-TIMER6_U6-PadU6)") (class "Default")
      (node (ref "U2") (pin "U6") (pinfunction "TIMER6_U6_U6") (pintype "bidirectional"))
    )
    (net (code "149") (name "unconnected-(U2B-TIMER7_T7-PadT7)") (class "Default")
      (node (ref "U2") (pin "T7") (pinfunction "TIMER7_T7_T7") (pintype "bidirectional"))
    )
    (net (code "150") (name "unconnected-(U2B-UART0_CTSN_E18-PadE18)") (class "Default")
      (node (ref "U2") (pin "E18") (pinfunction "UART0_CTSN_E18_E18") (pintype "bidirectional"))
    )
    (net (code "151") (name "unconnected-(U2B-UART0_RTSN_E17-PadE17)") (class "Default")
      (node (ref "U2") (pin "E17") (pinfunction "UART0_RTSN_E17_E17") (pintype "bidirectional"))
    )
    (net (code "152") (name "unconnected-(U2B-UART0_RXD_E15-PadE15)") (class "Default")
      (node (ref "U2") (pin "E15") (pinfunction "UART0_RXD_E15_E15") (pintype "bidirectional"))
    )
    (net (code "153") (name "unconnected-(U2B-UART0_TXD_E16-PadE16)") (class "Default")
      (node (ref "U2") (pin "E16") (pinfunction "UART0_TXD_E16_E16") (pintype "bidirectional"))
    )
    (net (code "154") (name "unconnected-(U2B-UART1_RXD_D16-PadD16)") (class "Default")
      (node (ref "U2") (pin "D16") (pinfunction "UART1_RXD_D16_D16") (pintype "bidirectional"))
    )
    (net (code "155") (name "unconnected-(U2B-UART1_TXD_D15-PadD15)") (class "Default")
      (node (ref "U2") (pin "D15") (pinfunction "UART1_TXD_D15_D15") (pintype "bidirectional"))
    )
    (net (code "156") (name "unconnected-(U2B-UART2_RXD_A17-PadA17)") (class "Default")
      (node (ref "U2") (pin "A17") (pinfunction "UART2_RXD_A17_A17") (pintype "bidirectional"))
    )
    (net (code "157") (name "unconnected-(U2B-UART2_TXD_B17-PadB17)") (class "Default")
      (node (ref "U2") (pin "B17") (pinfunction "UART2_TXD_B17_B17") (pintype "bidirectional"))
    )
    (net (code "158") (name "unconnected-(U2B-UART4_RXD_T17-PadT17)") (class "Default")
      (node (ref "U2") (pin "T17") (pinfunction "UART4_RXD_T17_T17") (pintype "bidirectional"))
    )
    (net (code "159") (name "unconnected-(U2B-UART4_TXD_U17-PadU17)") (class "Default")
      (node (ref "U2") (pin "U17") (pinfunction "UART4_TXD_U17_U17") (pintype "bidirectional"))
    )
    (net (code "160") (name "unconnected-(U2C-ADC_VREFP-PadB9)") (class "Default")
      (node (ref "U2") (pin "B9") (pinfunction "ADC_VREFP_B9") (pintype "bidirectional"))
    )
    (net (code "161") (name "unconnected-(U2C-AIN0-PadB6)") (class "Default")
      (node (ref "U2") (pin "B6") (pinfunction "AIN0_B6") (pintype "bidirectional"))
    )
    (net (code "162") (name "unconnected-(U2C-AIN1-PadC7)") (class "Default")
      (node (ref "U2") (pin "C7") (pinfunction "AIN1_C7") (pintype "bidirectional"))
    )
    (net (code "163") (name "unconnected-(U2C-AIN2-PadB7)") (class "Default")
      (node (ref "U2") (pin "B7") (pinfunction "AIN2_B7") (pintype "bidirectional"))
    )
    (net (code "164") (name "unconnected-(U2C-AIN3-PadA7)") (class "Default")
      (node (ref "U2") (pin "A7") (pinfunction "AIN3_A7") (pintype "bidirectional"))
    )
    (net (code "165") (name "unconnected-(U2C-AIN4-PadC8)") (class "Default")
      (node (ref "U2") (pin "C8") (pinfunction "AIN4_C8") (pintype "bidirectional"))
    )
    (net (code "166") (name "unconnected-(U2C-AIN5-PadB8)") (class "Default")
      (node (ref "U2") (pin "B8") (pinfunction "AIN5_B8") (pintype "bidirectional"))
    )
    (net (code "167") (name "unconnected-(U2C-AIN6-PadA8)") (class "Default")
      (node (ref "U2") (pin "A8") (pinfunction "AIN6_A8") (pintype "bidirectional"))
    )
    (net (code "168") (name "unconnected-(U2C-AIN7-PadC9)") (class "Default")
      (node (ref "U2") (pin "C9") (pinfunction "AIN7_C9") (pintype "bidirectional"))
    )
    (net (code "169") (name "unconnected-(U2C-HDMIDIS_GPIO1_27_V17-PadV17)") (class "Default")
      (node (ref "U2") (pin "V17") (pinfunction "HDMIDIS_GPIO1_27_V17_V17") (pintype "bidirectional"))
    )
    (net (code "170") (name "unconnected-(U2C-HDMIINT_GPIO1_25_U16-PadU16)") (class "Default")
      (node (ref "U2") (pin "U16") (pinfunction "HDMIINT_GPIO1_25_U16_U16") (pintype "bidirectional"))
    )
    (net (code "171") (name "unconnected-(U2C-LCD_DE_R6-PadR6)") (class "Default")
      (node (ref "U2") (pin "R6") (pinfunction "LCD_DE_R6_R6") (pintype "bidirectional"))
    )
    (net (code "172") (name "unconnected-(U2C-LCD_HSYNC_R5-PadR5)") (class "Default")
      (node (ref "U2") (pin "R5") (pinfunction "LCD_HSYNC_R5_R5") (pintype "bidirectional"))
    )
    (net (code "173") (name "unconnected-(U2C-LCD_PCLK_V5-PadV5)") (class "Default")
      (node (ref "U2") (pin "V5") (pinfunction "LCD_PCLK_V5_V5") (pintype "bidirectional"))
    )
    (net (code "174") (name "unconnected-(U2C-LCD_VSYNC_U5-PadU5)") (class "Default")
      (node (ref "U2") (pin "U5") (pinfunction "LCD_VSYNC_U5_U5") (pintype "bidirectional"))
    )
    (net (code "175") (name "unconnected-(U2C-USB0_CE-PadM15)") (class "Default")
      (node (ref "U2") (pin "M15") (pinfunction "USB0_CE_M15") (pintype "bidirectional"))
    )
    (net (code "176") (name "unconnected-(U2C-USB0_DRVVBUS-PadF16)") (class "Default")
      (node (ref "U2") (pin "F16") (pinfunction "USB0_DRVVBUS_F16") (pintype "bidirectional"))
    )
    (net (code "177") (name "unconnected-(U2C-USB1OC_GPIO1_26_T16-PadT16)") (class "Default")
      (node (ref "U2") (pin "T16") (pinfunction "USB1OC_GPIO1_26_T16_T16") (pintype "bidirectional"))
    )
    (net (code "178") (name "unconnected-(U2C-USB1_CE-PadP18)") (class "Default")
      (node (ref "U2") (pin "P18") (pinfunction "USB1_CE_P18") (pintype "bidirectional"))
    )
    (net (code "179") (name "unconnected-(U2C-USB1_DRVVBUS-PadF15)") (class "Default")
      (node (ref "U2") (pin "F15") (pinfunction "USB1_DRVVBUS_F15") (pintype "bidirectional"))
    )
    (net (code "180") (name "unconnected-(U2C-VOUT_ADC_1P8V_0-PadA4)") (class "Default")
      (node (ref "U2") (pin "A4") (pinfunction "VOUT_ADC_1P8V_0_A4") (pintype "bidirectional"))
    )
    (net (code "181") (name "unconnected-(U2C-VOUT_ADC_1P8V_1-PadA5)") (class "Default")
      (node (ref "U2") (pin "A5") (pinfunction "VOUT_ADC_1P8V_1_A5") (pintype "bidirectional"))
    )
    (net (code "182") (name "unconnected-(U2C-VSSA_ADC_0-PadA6)") (class "Default")
      (node (ref "U2") (pin "A6") (pinfunction "VSSA_ADC_0_A6") (pintype "bidirectional"))
    )
    (net (code "183") (name "unconnected-(U2C-VSSA_ADC_1-PadA9)") (class "Default")
      (node (ref "U2") (pin "A9") (pinfunction "VSSA_ADC_1_A9") (pintype "bidirectional"))
    )
    (net (code "184") (name "unconnected-(U2C-VSSA_ADC_2-PadE8)") (class "Default")
      (node (ref "U2") (pin "E8") (pinfunction "VSSA_ADC_2_E8") (pintype "bidirectional"))
    )
    (net (code "185") (name "unconnected-(U2E-CAP_VBB_MPU-PadC10)") (class "Default")
      (node (ref "U2") (pin "C10") (pinfunction "CAP_VBB_MPU_C10") (pintype "bidirectional"))
    )
    (net (code "186") (name "unconnected-(U2E-CAP_VDD_RTC-PadD6)") (class "Default")
      (node (ref "U2") (pin "D6") (pinfunction "CAP_VDD_RTC_D6") (pintype "bidirectional"))
    )
    (net (code "187") (name "unconnected-(U2E-CAP_VDD_SRAM_COR-PadD9)") (class "Default")
      (node (ref "U2") (pin "D9") (pinfunction "CAP_VDD_SRAM_COR_D9") (pintype "bidirectional"))
    )
    (net (code "188") (name "unconnected-(U2E-CAP_VDD_SRAM_MPU-PadD11)") (class "Default")
      (node (ref "U2") (pin "D11") (pinfunction "CAP_VDD_SRAM_MPU_D11") (pintype "bidirectional"))
    )
    (net (code "189") (name "unconnected-(U2E-TESTOUT-PadA3)") (class "Default")
      (node (ref "U2") (pin "A3") (pinfunction "TESTOUT_A3") (pintype "bidirectional"))
    )
    (net (code "190") (name "unconnected-(U2E-VDDA_ADC-PadD8)") (class "Default")
      (node (ref "U2") (pin "D8") (pinfunction "VDDA_ADC_D8") (pintype "bidirectional"))
    )
    (net (code "191") (name "unconnected-(U2E-VDDS_DDR1-PadE5)") (class "Default")
      (node (ref "U2") (pin "E5") (pinfunction "VDDS_DDR1_E5") (pintype "bidirectional"))
    )
    (net (code "192") (name "unconnected-(U2E-VDDS_DDR2-PadF5)") (class "Default")
      (node (ref "U2") (pin "F5") (pinfunction "VDDS_DDR2_F5") (pintype "bidirectional"))
    )
    (net (code "193") (name "unconnected-(U2E-VDDS_DDR3-PadG5)") (class "Default")
      (node (ref "U2") (pin "G5") (pinfunction "VDDS_DDR3_G5") (pintype "bidirectional"))
    )
    (net (code "194") (name "unconnected-(U2E-VDDS_DDR4-PadH5)") (class "Default")
      (node (ref "U2") (pin "H5") (pinfunction "VDDS_DDR4_H5") (pintype "bidirectional"))
    )
    (net (code "195") (name "unconnected-(U2E-VDDS_DDR5-PadJ5)") (class "Default")
      (node (ref "U2") (pin "J5") (pinfunction "VDDS_DDR5_J5") (pintype "bidirectional"))
    )
    (net (code "196") (name "unconnected-(U2E-VDDS_DDR6-PadK5)") (class "Default")
      (node (ref "U2") (pin "K5") (pinfunction "VDDS_DDR6_K5") (pintype "bidirectional"))
    )
    (net (code "197") (name "unconnected-(U2E-VDDS_DDR7-PadL5)") (class "Default")
      (node (ref "U2") (pin "L5") (pinfunction "VDDS_DDR7_L5") (pintype "bidirectional"))
    )
    (net (code "198") (name "unconnected-(U2E-VDD_1V83-PadE9)") (class "Default")
      (node (ref "U2") (pin "E9") (pinfunction "VDD_1V83_E9") (pintype "bidirectional"))
    )
    (net (code "199") (name "unconnected-(U2E-VDD_1V84-PadD10)") (class "Default")
      (node (ref "U2") (pin "D10") (pinfunction "VDD_1V84_D10") (pintype "bidirectional"))
    )
    (net (code "200") (name "unconnected-(U2E-VDD_3V3A1-PadE10)") (class "Default")
      (node (ref "U2") (pin "E10") (pinfunction "VDD_3V3A1_E10") (pintype "bidirectional"))
    )
    (net (code "201") (name "unconnected-(U2E-VDD_3V3A2-PadE11)") (class "Default")
      (node (ref "U2") (pin "E11") (pinfunction "VDD_3V3A2_E11") (pintype "bidirectional"))
    )
    (net (code "202") (name "unconnected-(U2E-VDD_3V3A3-PadE12)") (class "Default")
      (node (ref "U2") (pin "E12") (pinfunction "VDD_3V3A3_E12") (pintype "bidirectional"))
    )
    (net (code "203") (name "unconnected-(U2E-VDD_3V3A4-PadE13)") (class "Default")
      (node (ref "U2") (pin "E13") (pinfunction "VDD_3V3A4_E13") (pintype "bidirectional"))
    )
    (net (code "204") (name "unconnected-(U2E-VDD_3V3A5-PadF14)") (class "Default")
      (node (ref "U2") (pin "F14") (pinfunction "VDD_3V3A5_F14") (pintype "bidirectional"))
    )
    (net (code "205") (name "unconnected-(U2E-VDD_3V3A6-PadG14)") (class "Default")
      (node (ref "U2") (pin "G14") (pinfunction "VDD_3V3A6_G14") (pintype "bidirectional"))
    )
    (net (code "206") (name "unconnected-(U2E-VDD_3V3A7-PadH14)") (class "Default")
      (node (ref "U2") (pin "H14") (pinfunction "VDD_3V3A7_H14") (pintype "bidirectional"))
    )
    (net (code "207") (name "unconnected-(U2E-VDD_3V3A8-PadJ14)") (class "Default")
      (node (ref "U2") (pin "J14") (pinfunction "VDD_3V3A8_J14") (pintype "bidirectional"))
    )
    (net (code "208") (name "unconnected-(U2E-VDD_3V3A9-PadK14)") (class "Default")
      (node (ref "U2") (pin "K14") (pinfunction "VDD_3V3A9_K14") (pintype "bidirectional"))
    )
    (net (code "209") (name "unconnected-(U2E-VDD_3V3A10-PadL14)") (class "Default")
      (node (ref "U2") (pin "L14") (pinfunction "VDD_3V3A10_L14") (pintype "bidirectional"))
    )
    (net (code "210") (name "unconnected-(U2E-VDD_3V3A11-PadN5)") (class "Default")
      (node (ref "U2") (pin "N5") (pinfunction "VDD_3V3A11_N5") (pintype "bidirectional"))
    )
    (net (code "211") (name "unconnected-(U2E-VDD_3V3A12-PadN15)") (class "Default")
      (node (ref "U2") (pin "N15") (pinfunction "VDD_3V3A12_N15") (pintype "bidirectional"))
    )
    (net (code "212") (name "unconnected-(U2E-VDD_3V3A13-PadP5)") (class "Default")
      (node (ref "U2") (pin "P5") (pinfunction "VDD_3V3A13_P5") (pintype "bidirectional"))
    )
    (net (code "213") (name "unconnected-(U2E-VDD_3V3A14-PadP6)") (class "Default")
      (node (ref "U2") (pin "P6") (pinfunction "VDD_3V3A14_P6") (pintype "bidirectional"))
    )
    (net (code "214") (name "unconnected-(U2E-VDD_3V3A15-PadP7)") (class "Default")
      (node (ref "U2") (pin "P7") (pinfunction "VDD_3V3A15_P7") (pintype "bidirectional"))
    )
    (net (code "215") (name "unconnected-(U2E-VDD_3V3A16-PadP8)") (class "Default")
      (node (ref "U2") (pin "P8") (pinfunction "VDD_3V3A16_P8") (pintype "bidirectional"))
    )
    (net (code "216") (name "unconnected-(U2E-VDD_3V3A17-PadP10)") (class "Default")
      (node (ref "U2") (pin "P10") (pinfunction "VDD_3V3A17_P10") (pintype "bidirectional"))
    )
    (net (code "217") (name "unconnected-(U2E-VDD_3V3A18-PadP11)") (class "Default")
      (node (ref "U2") (pin "P11") (pinfunction "VDD_3V3A18_P11") (pintype "bidirectional"))
    )
    (net (code "218") (name "unconnected-(U2E-VDD_3V3A19-PadP12)") (class "Default")
      (node (ref "U2") (pin "P12") (pinfunction "VDD_3V3A19_P12") (pintype "bidirectional"))
    )
    (net (code "219") (name "unconnected-(U2E-VDD_3V3A20-PadP13)") (class "Default")
      (node (ref "U2") (pin "P13") (pinfunction "VDD_3V3A20_P13") (pintype "bidirectional"))
    )
    (net (code "220") (name "unconnected-(U2E-VDD_3V3A21-PadR15)") (class "Default")
      (node (ref "U2") (pin "R15") (pinfunction "VDD_3V3A21_R15") (pintype "bidirectional"))
    )
    (net (code "221") (name "unconnected-(U2E-VDD_CORE1-PadF6)") (class "Default")
      (node (ref "U2") (pin "F6") (pinfunction "VDD_CORE1_F6") (pintype "bidirectional"))
    )
    (net (code "222") (name "unconnected-(U2E-VDD_CORE2-PadF7)") (class "Default")
      (node (ref "U2") (pin "F7") (pinfunction "VDD_CORE2_F7") (pintype "bidirectional"))
    )
    (net (code "223") (name "unconnected-(U2E-VDD_CORE3-PadG6)") (class "Default")
      (node (ref "U2") (pin "G6") (pinfunction "VDD_CORE3_G6") (pintype "bidirectional"))
    )
    (net (code "224") (name "unconnected-(U2E-VDD_CORE4-PadG7)") (class "Default")
      (node (ref "U2") (pin "G7") (pinfunction "VDD_CORE4_G7") (pintype "bidirectional"))
    )
    (net (code "225") (name "unconnected-(U2E-VDD_CORE5-PadG10)") (class "Default")
      (node (ref "U2") (pin "G10") (pinfunction "VDD_CORE5_G10") (pintype "bidirectional"))
    )
    (net (code "226") (name "unconnected-(U2E-VDD_CORE6-PadH11)") (class "Default")
      (node (ref "U2") (pin "H11") (pinfunction "VDD_CORE6_H11") (pintype "bidirectional"))
    )
    (net (code "227") (name "unconnected-(U2E-VDD_CORE7-PadJ12)") (class "Default")
      (node (ref "U2") (pin "J12") (pinfunction "VDD_CORE7_J12") (pintype "bidirectional"))
    )
    (net (code "228") (name "unconnected-(U2E-VDD_CORE8-PadK6)") (class "Default")
      (node (ref "U2") (pin "K6") (pinfunction "VDD_CORE8_K6") (pintype "bidirectional"))
    )
    (net (code "229") (name "unconnected-(U2E-VDD_CORE9-PadK8)") (class "Default")
      (node (ref "U2") (pin "K8") (pinfunction "VDD_CORE9_K8") (pintype "bidirectional"))
    )
    (net (code "230") (name "unconnected-(U2E-VDD_CORE10-PadK12)") (class "Default")
      (node (ref "U2") (pin "K12") (pinfunction "VDD_CORE10_K12") (pintype "bidirectional"))
    )
    (net (code "231") (name "unconnected-(U2E-VDD_CORE11-PadL6)") (class "Default")
      (node (ref "U2") (pin "L6") (pinfunction "VDD_CORE11_L6") (pintype "bidirectional"))
    )
    (net (code "232") (name "unconnected-(U2E-VDD_CORE12-PadL7)") (class "Default")
      (node (ref "U2") (pin "L7") (pinfunction "VDD_CORE12_L7") (pintype "bidirectional"))
    )
    (net (code "233") (name "unconnected-(U2E-VDD_CORE13-PadL8)") (class "Default")
      (node (ref "U2") (pin "L8") (pinfunction "VDD_CORE13_L8") (pintype "bidirectional"))
    )
    (net (code "234") (name "unconnected-(U2E-VDD_CORE14-PadL9)") (class "Default")
      (node (ref "U2") (pin "L9") (pinfunction "VDD_CORE14_L9") (pintype "bidirectional"))
    )
    (net (code "235") (name "unconnected-(U2E-VDD_CORE15-PadM11)") (class "Default")
      (node (ref "U2") (pin "M11") (pinfunction "VDD_CORE15_M11") (pintype "bidirectional"))
    )
    (net (code "236") (name "unconnected-(U2E-VDD_CORE16-PadM13)") (class "Default")
      (node (ref "U2") (pin "M13") (pinfunction "VDD_CORE16_M13") (pintype "bidirectional"))
    )
    (net (code "237") (name "unconnected-(U2E-VDD_CORE17-PadN8)") (class "Default")
      (node (ref "U2") (pin "N8") (pinfunction "VDD_CORE17_N8") (pintype "bidirectional"))
    )
    (net (code "238") (name "unconnected-(U2E-VDD_CORE18-PadN9)") (class "Default")
      (node (ref "U2") (pin "N9") (pinfunction "VDD_CORE18_N9") (pintype "bidirectional"))
    )
    (net (code "239") (name "unconnected-(U2E-VDD_CORE19-PadN12)") (class "Default")
      (node (ref "U2") (pin "N12") (pinfunction "VDD_CORE19_N12") (pintype "bidirectional"))
    )
    (net (code "240") (name "unconnected-(U2E-VDD_CORE20-PadN13)") (class "Default")
      (node (ref "U2") (pin "N13") (pinfunction "VDD_CORE20_N13") (pintype "bidirectional"))
    )
    (net (code "241") (name "unconnected-(U2E-VDD_MPU0-PadF10)") (class "Default")
      (node (ref "U2") (pin "F10") (pinfunction "VDD_MPU0_F10") (pintype "bidirectional"))
    )
    (net (code "242") (name "unconnected-(U2E-VDD_MPU1-PadF11)") (class "Default")
      (node (ref "U2") (pin "F11") (pinfunction "VDD_MPU1_F11") (pintype "bidirectional"))
    )
    (net (code "243") (name "unconnected-(U2E-VDD_MPU2-PadF12)") (class "Default")
      (node (ref "U2") (pin "F12") (pinfunction "VDD_MPU2_F12") (pintype "bidirectional"))
    )
    (net (code "244") (name "unconnected-(U2E-VDD_MPU3-PadF13)") (class "Default")
      (node (ref "U2") (pin "F13") (pinfunction "VDD_MPU3_F13") (pintype "bidirectional"))
    )
    (net (code "245") (name "unconnected-(U2E-VDD_MPU4-PadG13)") (class "Default")
      (node (ref "U2") (pin "G13") (pinfunction "VDD_MPU4_G13") (pintype "bidirectional"))
    )
    (net (code "246") (name "unconnected-(U2E-VDD_MPU5-PadH13)") (class "Default")
      (node (ref "U2") (pin "H13") (pinfunction "VDD_MPU5_H13") (pintype "bidirectional"))
    )
    (net (code "247") (name "unconnected-(U2E-VDD_MPU6-PadJ13)") (class "Default")
      (node (ref "U2") (pin "J13") (pinfunction "VDD_MPU6_J13") (pintype "bidirectional"))
    )
    (net (code "248") (name "unconnected-(U2E-VDD_MPU_MON-PadA2)") (class "Default")
      (node (ref "U2") (pin "A2") (pinfunction "VDD_MPU_MON_A2") (pintype "bidirectional"))
    )
    (net (code "249") (name "unconnected-(U2E-VDD_PLL1-PadE7)") (class "Default")
      (node (ref "U2") (pin "E7") (pinfunction "VDD_PLL1_E7") (pintype "bidirectional"))
    )
    (net (code "250") (name "unconnected-(U2E-VDD_PLL2-PadH15)") (class "Default")
      (node (ref "U2") (pin "H15") (pinfunction "VDD_PLL2_H15") (pintype "bidirectional"))
    )
    (net (code "251") (name "unconnected-(U2E-VDD_PLL3-PadR10)") (class "Default")
      (node (ref "U2") (pin "R10") (pinfunction "VDD_PLL3_R10") (pintype "bidirectional"))
    )
    (net (code "252") (name "unconnected-(U2E-VDD_PLL4-PadR11)") (class "Default")
      (node (ref "U2") (pin "R11") (pinfunction "VDD_PLL4_R11") (pintype "bidirectional"))
    )
    (net (code "253") (name "unconnected-(U2E-VDD_RTC1-PadD7)") (class "Default")
      (node (ref "U2") (pin "D7") (pinfunction "VDD_RTC1_D7") (pintype "bidirectional"))
    )
    (net (code "254") (name "unconnected-(U2E-VDD_RTC2-PadE6)") (class "Default")
      (node (ref "U2") (pin "E6") (pinfunction "VDD_RTC2_E6") (pintype "bidirectional"))
    )
    (net (code "255") (name "unconnected-(U2E-VDD_RTC4-PadF9)") (class "Default")
      (node (ref "U2") (pin "F9") (pinfunction "VDD_RTC4_F9") (pintype "bidirectional"))
    )
    (net (code "256") (name "unconnected-(U2E-VDD_RTC5-PadK13)") (class "Default")
      (node (ref "U2") (pin "K13") (pinfunction "VDD_RTC5_K13") (pintype "bidirectional"))
    )
    (net (code "257") (name "unconnected-(U2E-VDD_RTC6-PadN6)") (class "Default")
      (node (ref "U2") (pin "N6") (pinfunction "VDD_RTC6_N6") (pintype "bidirectional"))
    )
    (net (code "258") (name "unconnected-(U2E-VDD_RTC7-PadP9)") (class "Default")
      (node (ref "U2") (pin "P9") (pinfunction "VDD_RTC7_P9") (pintype "bidirectional"))
    )
    (net (code "259") (name "unconnected-(U2E-VDD_RTC8-PadP14)") (class "Default")
      (node (ref "U2") (pin "P14") (pinfunction "VDD_RTC8_P14") (pintype "bidirectional"))
    )
    (net (code "260") (name "unconnected-(U2E-VPP-PadM5)") (class "Default")
      (node (ref "U2") (pin "M5") (pinfunction "VPP_M5") (pintype "bidirectional"))
    )
    (net (code "261") (name "unconnected-(U3-NC-Pad1)") (class "Default")
      (node (ref "U3") (pin "1") (pinfunction "NC_1") (pintype "passive"))
    )
  )
)
